# Sheet_1.net
KiCad netlist of a schematic drawn in EasyEDA
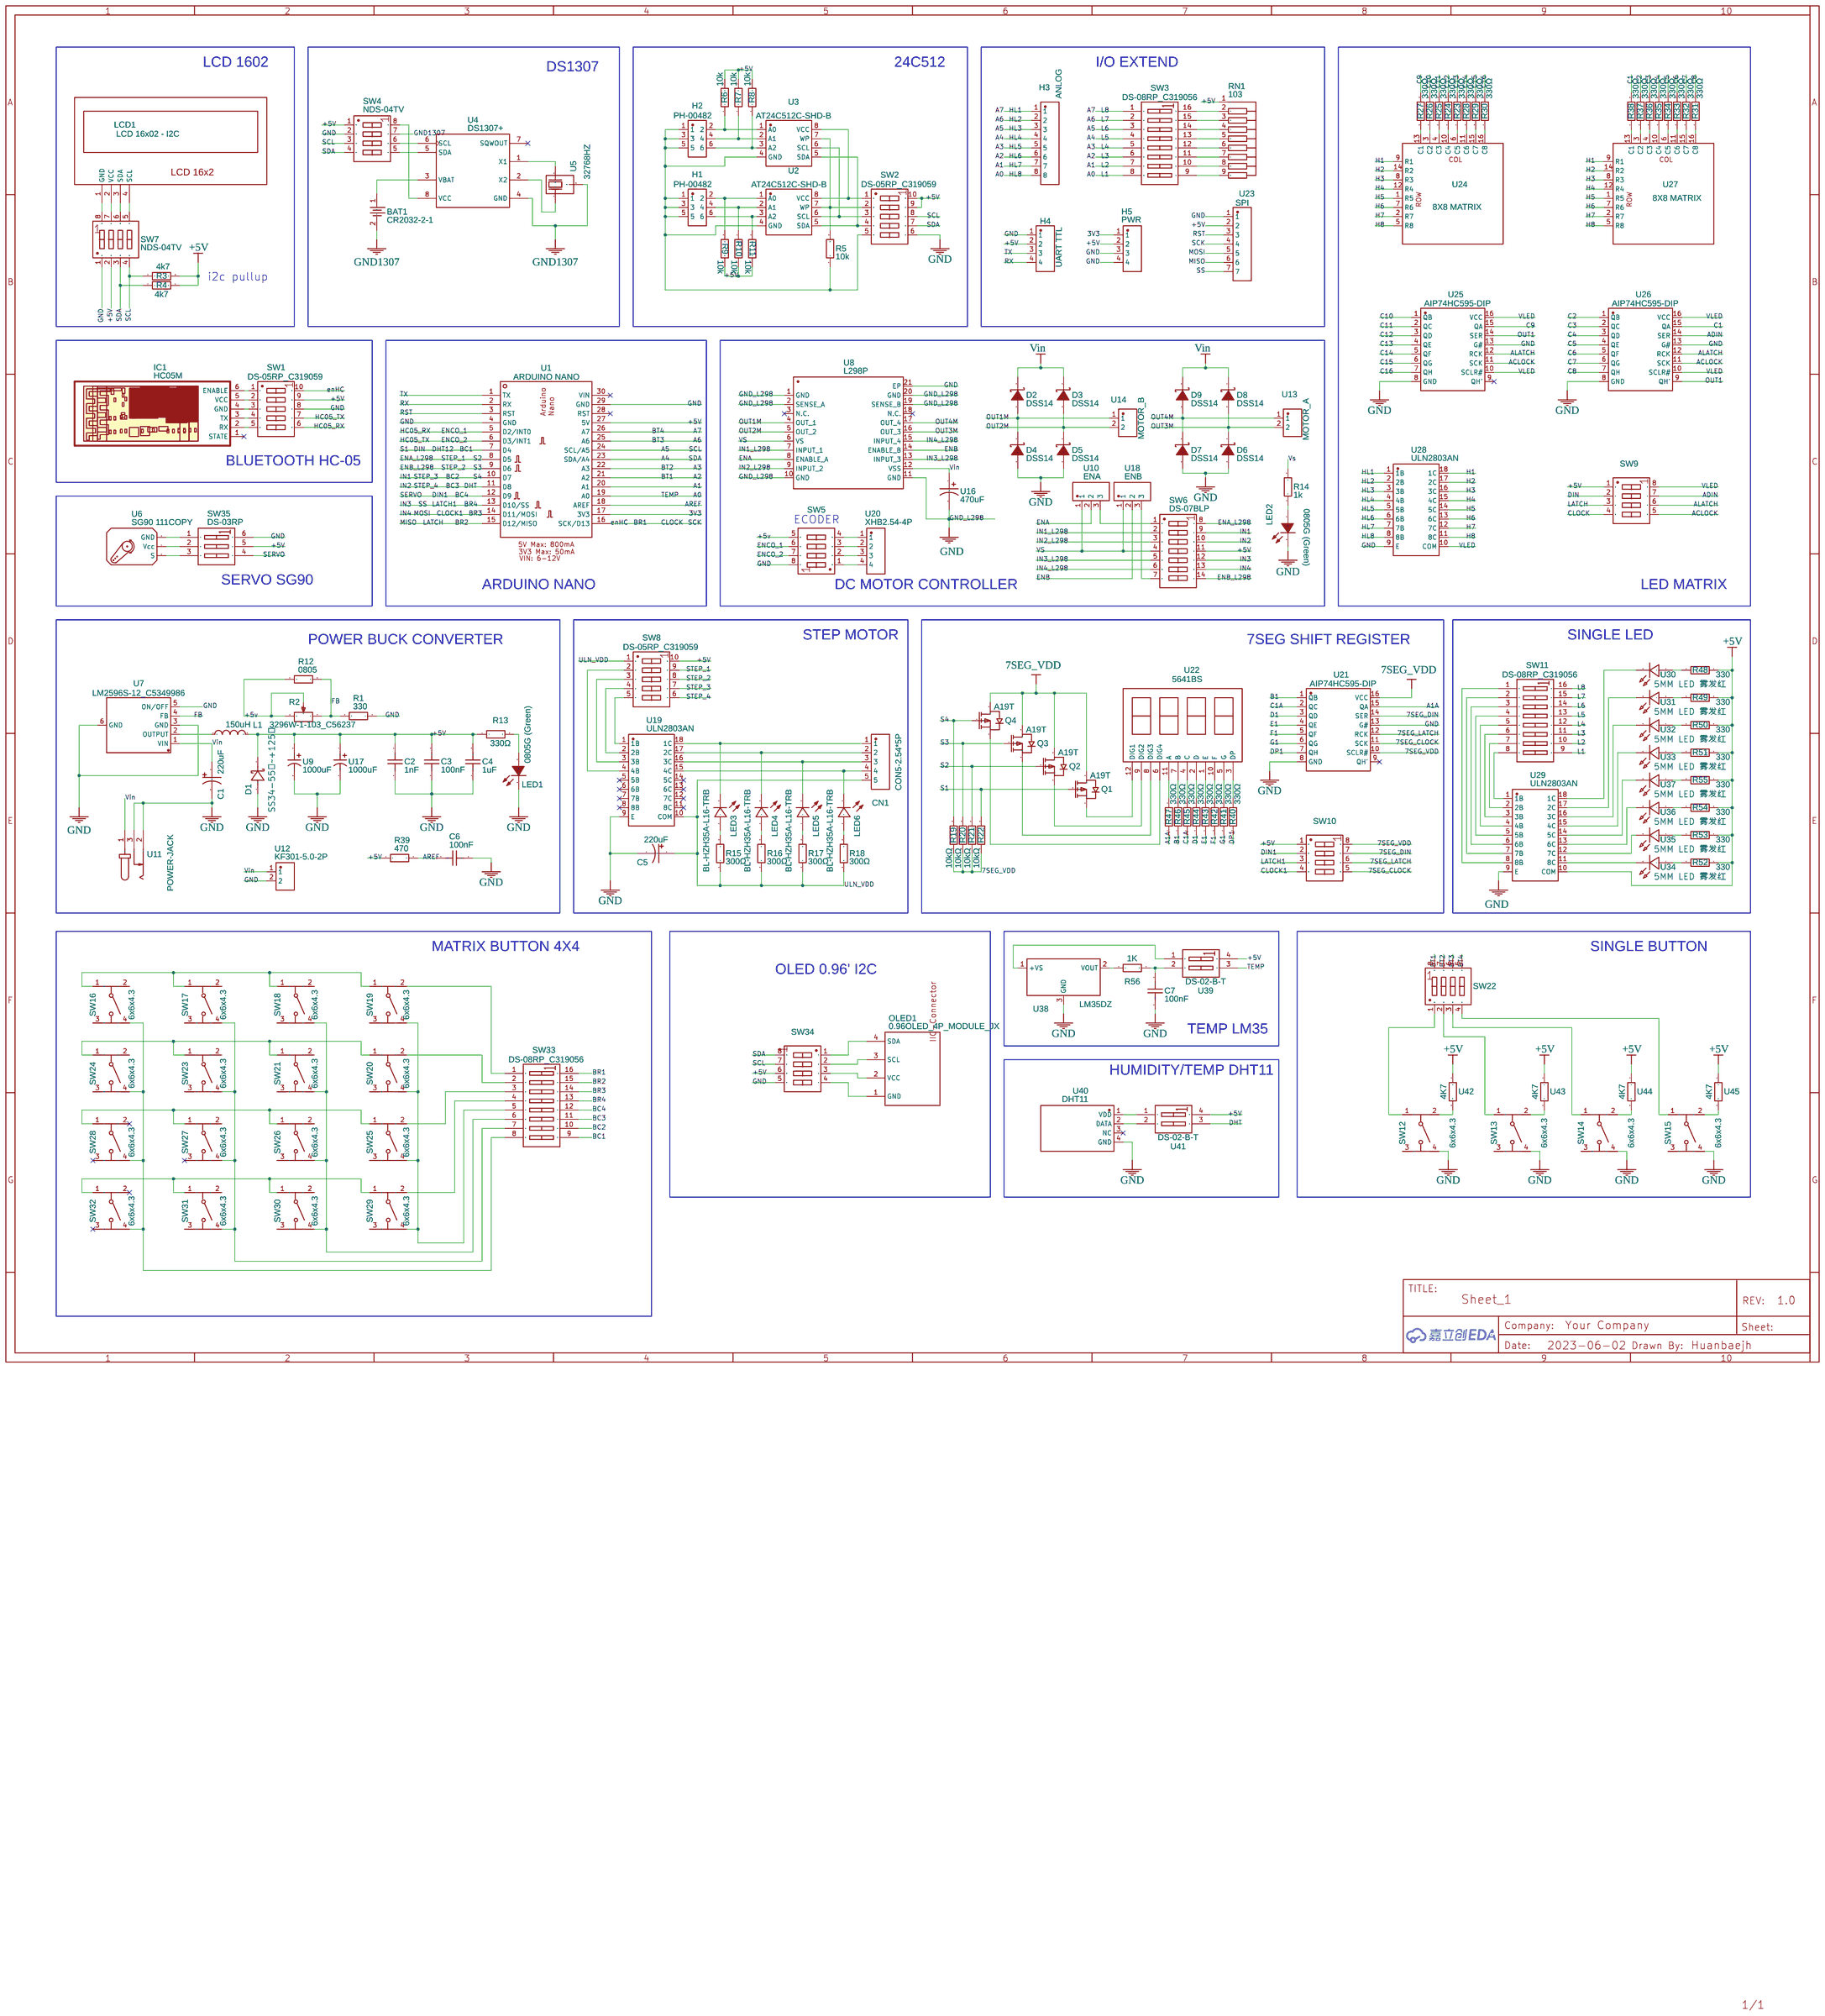
[diagram p0: schematic sheet]

(export (version "E")
  (design (tool "Eeschema 10.0.6"))
  (components
    (comp (ref "BAT1")
      (value "CR2032-2-1")
      (fields (field (name "BOM_Supplier Part") "C9900018737"))
      (libsource (lib "") (part "CR2032-2-1"))
    )
    (comp (ref "C1")
      (value "220uF")
      (fields
        (field (name "BOM_Manufacturer Part") "VUK221M1HTR-1316")
        (field (name "BOM_Supplier Part") "C335057")
      )
      (libsource (lib "") (part "VUK221M1HTR-1316"))
    )
    (comp (ref "C2")
      (value "1nF")
      (fields
        (field (name "BOM_Manufacturer Part") "C0805X102K101T")
        (field (name "BOM_Supplier Part") "C559288")
      )
      (libsource (lib "") (part "C0805X102K101T"))
    )
    (comp (ref "C3")
      (value "100nF")
      (fields
        (field (name "BOM_Manufacturer Part") "0805B104K101AT")
        (field (name "BOM_Supplier Part") "C3037660")
      )
      (libsource (lib "") (part "0805B104K101AT_2"))
    )
    (comp (ref "C4")
      (value "1uF")
      (fields
        (field (name "BOM_Manufacturer Part") "GRM219R71E105KA88D")
        (field (name "BOM_Supplier Part") "C86035")
      )
      (libsource (lib "") (part "GRM219R71E105KA88D"))
    )
    (comp (ref "C5")
      (value "220uF")
      (fields
        (field (name "BOM_Manufacturer Part") "EEEFC1C221AP")
        (field (name "BOM_Supplier Part") "C401620")
      )
      (libsource (lib "") (part "EEEFC1C221AP"))
    )
    (comp (ref "C6")
      (value "100nF")
      (fields
        (field (name "BOM_Manufacturer Part") "0805B104K101AT")
        (field (name "BOM_Supplier Part") "C3037660")
      )
      (libsource (lib "") (part "0805B104K101AT"))
    )
    (comp (ref "C7")
      (value "100nF")
      (fields
        (field (name "BOM_Manufacturer Part") "0805B104K101AT")
        (field (name "BOM_Supplier Part") "C3037660")
      )
      (libsource (lib "") (part "0805B104K101AT_1"))
    )
    (comp (ref "CN1")
      (value "CON5-2.54*5P")
      (fields (field (name "BOM_Supplier Part") "C9900003233"))
      (libsource (lib "") (part "CON5-2.54*5P"))
    )
    (comp (ref "D1")
      (value "SS34-55℃~+125℃")
      (fields
        (field (name "BOM_Manufacturer Part") "SS34-55℃&#126;+125℃")
        (field (name "BOM_Supplier Part") "C9900022445")
      )
      (libsource (lib "") (part "SS34-55℃&#126;+125℃"))
    )
    (comp (ref "D2")
      (value "DSS14")
      (fields (field (name "BOM_Supplier Part") "C59293"))
      (libsource (lib "") (part "DSS14"))
    )
    (comp (ref "D3")
      (value "DSS14")
      (fields (field (name "BOM_Supplier Part") "C59293"))
      (libsource (lib "") (part "DSS14"))
    )
    (comp (ref "D4")
      (value "DSS14")
      (fields (field (name "BOM_Supplier Part") "C59293"))
      (libsource (lib "") (part "DSS14"))
    )
    (comp (ref "D5")
      (value "DSS14")
      (fields (field (name "BOM_Supplier Part") "C59293"))
      (libsource (lib "") (part "DSS14"))
    )
    (comp (ref "D6")
      (value "DSS14")
      (fields (field (name "BOM_Supplier Part") "C59293"))
      (libsource (lib "") (part "DSS14"))
    )
    (comp (ref "D7")
      (value "DSS14")
      (fields (field (name "BOM_Supplier Part") "C59293"))
      (libsource (lib "") (part "DSS14"))
    )
    (comp (ref "D8")
      (value "DSS14")
      (fields (field (name "BOM_Supplier Part") "C59293"))
      (libsource (lib "") (part "DSS14"))
    )
    (comp (ref "D9")
      (value "DSS14")
      (fields (field (name "BOM_Supplier Part") "C59293"))
      (libsource (lib "") (part "DSS14"))
    )
    (comp (ref "H1")
      (value "PH-00482")
      (fields (field (name "BOM_Supplier Part") "C2685163"))
      (libsource (lib "") (part "PH-00482"))
    )
    (comp (ref "H2")
      (value "PH-00482")
      (fields (field (name "BOM_Supplier Part") "C2685163"))
      (libsource (lib "") (part "PH-00482"))
    )
    (comp (ref "H3")
      (value "ANLOG")
      (fields
        (field (name "BOM_Manufacturer Part") "X5511WV-08-C396D43-1220")
        (field (name "BOM_Supplier Part") "C2883395")
      )
      (libsource (lib "") (part "X5511WV-08-C396D43-1220"))
    )
    (comp (ref "H4")
      (value "UART TTL")
      (fields
        (field (name "BOM_Manufacturer Part") "A2541HWV-4P")
        (field (name "BOM_Supplier Part") "C5144876")
      )
      (libsource (lib "") (part "A2541HWV-4P_C5144876"))
    )
    (comp (ref "H5")
      (value "PWR")
      (fields
        (field (name "BOM_Manufacturer Part") "DZ254R-11-04-63")
        (field (name "BOM_Supplier Part") "C2935910")
      )
      (libsource (lib "") (part "DZ254R-11-04-63"))
    )
    (comp (ref "IC1") (value "HC05M") (libsource (lib "") (part "HC05M")))
    (comp (ref "L1")
      (value "150uH")
      (fields
        (field (name "BOM_Manufacturer Part") "SWRH1205B-151MT")
        (field (name "BOM_Supplier Part") "C127794")
      )
      (libsource (lib "") (part "SWRH1205B-151MT"))
    )
    (comp (ref "LCD1")
      (value "LCD 16x02 - I2C")
      (fields
        (field (name "BOM_Manufacturer Part") "LCM1602K-NSW-BBW-33V33")
        (field (name "BOM_Supplier Part") "C83272")
      )
      (libsource (lib "") (part "LCD 16x02 - I2C"))
    )
    (comp (ref "LED1")
      (value "0805G (Green)")
      (fields (field (name "BOM_Manufacturer Part") "KT-0805翠绿") (field (name "BOM_Supplier Part") "C2297"))
      (libsource (lib "") (part "0805G (Green)"))
    )
    (comp (ref "LED2")
      (value "0805G (Green)")
      (fields (field (name "BOM_Manufacturer Part") "KT-0805翠绿") (field (name "BOM_Supplier Part") "C2297"))
      (libsource (lib "") (part "0805G (Green)"))
    )
    (comp (ref "LED3")
      (value "BL-HZH35A-L16-TRB")
      (fields (field (name "BOM_Supplier Part") "C138554"))
      (libsource (lib "") (part "BL-HZH35A-L16-TRB"))
    )
    (comp (ref "LED4")
      (value "BL-HZH35A-L16-TRB")
      (fields (field (name "BOM_Supplier Part") "C138554"))
      (libsource (lib "") (part "BL-HZH35A-L16-TRB"))
    )
    (comp (ref "LED5")
      (value "BL-HZH35A-L16-TRB")
      (fields (field (name "BOM_Supplier Part") "C138554"))
      (libsource (lib "") (part "BL-HZH35A-L16-TRB"))
    )
    (comp (ref "LED6")
      (value "BL-HZH35A-L16-TRB")
      (fields (field (name "BOM_Supplier Part") "C138554"))
      (libsource (lib "") (part "BL-HZH35A-L16-TRB"))
    )
    (comp (ref "OLED1")
      (value "0.96OLED_4P_MODULE_JX")
      (fields (field (name "BOM_Supplier Part") "C9900004566"))
      (libsource (lib "") (part "0.96OLED_4P_MODULE_JX"))
    )
    (comp (ref "Q1")
      (value "A19T")
      (fields (field (name "BOM_Manufacturer Part") "FS3401M") (field (name "BOM_Supplier Part") "C2936839"))
      (libsource (lib "") (part "FS3401MLT1 A19T"))
    )
    (comp (ref "Q2")
      (value "A19T")
      (fields (field (name "BOM_Manufacturer Part") "FS3401M") (field (name "BOM_Supplier Part") "C2936839"))
      (libsource (lib "") (part "FS3401MLT1 A19T"))
    )
    (comp (ref "Q3")
      (value "A19T")
      (fields (field (name "BOM_Manufacturer Part") "FS3401M") (field (name "BOM_Supplier Part") "C2936839"))
      (libsource (lib "") (part "FS3401MLT1 A19T"))
    )
    (comp (ref "Q4")
      (value "A19T")
      (fields (field (name "BOM_Manufacturer Part") "FS3401M") (field (name "BOM_Supplier Part") "C2936839"))
      (libsource (lib "") (part "FS3401MLT1 A19T"))
    )
    (comp (ref "R1")
      (value "330")
      (fields
        (field (name "BOM_Manufacturer Part") "CR0805F833R2G")
        (field (name "BOM_Supplier Part") "C101670")
      )
      (libsource (lib "") (part "CR0805F833R2G"))
    )
    (comp (ref "R2")
      (value "3296W-1-103_C56237")
      (fields
        (field (name "BOM_Manufacturer Part") "3296W-1-103")
        (field (name "BOM_Supplier Part") "C56237")
      )
      (libsource (lib "") (part "3296W-1-103_C56237"))
    )
    (comp (ref "R3")
      (value "4k7")
      (fields
        (field (name "BOM_Manufacturer Part") "AECR0805F24K0K9")
        (field (name "BOM_Supplier Part") "C352238")
      )
      (libsource (lib "") (part "AECR0805F24K0K9"))
    )
    (comp (ref "R4")
      (value "4k7")
      (fields
        (field (name "BOM_Manufacturer Part") "AECR0805F24K0K9")
        (field (name "BOM_Supplier Part") "C352238")
      )
      (libsource (lib "") (part "AECR0805F24K0K9"))
    )
    (comp (ref "R5")
      (value "10k")
      (fields
        (field (name "BOM_Manufacturer Part") "CR0805F12K7P05Z")
        (field (name "BOM_Supplier Part") "C245233")
      )
      (libsource (lib "") (part "CR0805F12K7P05"))
    )
    (comp (ref "R6")
      (value "10k")
      (fields
        (field (name "BOM_Manufacturer Part") "CR0805F12K7P05Z")
        (field (name "BOM_Supplier Part") "C245233")
      )
      (libsource (lib "") (part "CR0805F12K7P05"))
    )
    (comp (ref "R7")
      (value "10k")
      (fields
        (field (name "BOM_Manufacturer Part") "CR0805F12K7P05Z")
        (field (name "BOM_Supplier Part") "C245233")
      )
      (libsource (lib "") (part "CR0805F12K7P05"))
    )
    (comp (ref "R8")
      (value "10k")
      (fields
        (field (name "BOM_Manufacturer Part") "CR0805F12K7P05Z")
        (field (name "BOM_Supplier Part") "C245233")
      )
      (libsource (lib "") (part "CR0805F12K7P05"))
    )
    (comp (ref "R9")
      (value "10k")
      (fields
        (field (name "BOM_Manufacturer Part") "CR0805F12K7P05Z")
        (field (name "BOM_Supplier Part") "C245233")
      )
      (libsource (lib "") (part "CR0805F12K7P05_1"))
    )
    (comp (ref "R10")
      (value "10k")
      (fields
        (field (name "BOM_Manufacturer Part") "CR0805F12K7P05Z")
        (field (name "BOM_Supplier Part") "C245233")
      )
      (libsource (lib "") (part "CR0805F12K7P05_1"))
    )
    (comp (ref "R11")
      (value "10k")
      (fields
        (field (name "BOM_Manufacturer Part") "CR0805F12K7P05Z")
        (field (name "BOM_Supplier Part") "C245233")
      )
      (libsource (lib "") (part "CR0805F12K7P05_1"))
    )
    (comp (ref "R12")
      (value "0805")
      (fields (field (name "BOM_Supplier Part") "C9900012715"))
      (libsource (lib "") (part "0805"))
    )
    (comp (ref "R13")
      (value "330Ω")
      (fields
        (field (name "BOM_Manufacturer Part") "AECR0805F130RK9")
        (field (name "BOM_Supplier Part") "C352269")
      )
      (libsource (lib "") (part "AECR0805F130RK9"))
    )
    (comp (ref "R14")
      (value "1k")
      (fields
        (field (name "BOM_Manufacturer Part") "AECR0805F130RK9")
        (field (name "BOM_Supplier Part") "C352269")
      )
      (libsource (lib "") (part "AECR0805F130RK9_1"))
    )
    (comp (ref "R15")
      (value "300Ω")
      (fields
        (field (name "BOM_Manufacturer Part") "AECR0805F300RK9")
        (field (name "BOM_Supplier Part") "C352224")
      )
      (libsource (lib "") (part "AECR0805F300RK9"))
    )
    (comp (ref "R16")
      (value "300Ω")
      (fields
        (field (name "BOM_Manufacturer Part") "AECR0805F300RK9")
        (field (name "BOM_Supplier Part") "C352224")
      )
      (libsource (lib "") (part "AECR0805F300RK9"))
    )
    (comp (ref "R17")
      (value "300Ω")
      (fields
        (field (name "BOM_Manufacturer Part") "AECR0805F300RK9")
        (field (name "BOM_Supplier Part") "C352224")
      )
      (libsource (lib "") (part "AECR0805F300RK9"))
    )
    (comp (ref "R18")
      (value "300Ω")
      (fields
        (field (name "BOM_Manufacturer Part") "AECR0805F300RK9")
        (field (name "BOM_Supplier Part") "C352224")
      )
      (libsource (lib "") (part "AECR0805F300RK9"))
    )
    (comp (ref "R19")
      (value "10kΩ")
      (fields
        (field (name "BOM_Manufacturer Part") "0805WAD1002T5E")
        (field (name "BOM_Supplier Part") "C169071")
      )
      (libsource (lib "") (part "0805WAD1002T5E"))
    )
    (comp (ref "R20")
      (value "10kΩ")
      (fields
        (field (name "BOM_Manufacturer Part") "0805WAD1002T5E")
        (field (name "BOM_Supplier Part") "C169071")
      )
      (libsource (lib "") (part "0805WAD1002T5E"))
    )
    (comp (ref "R21")
      (value "10kΩ")
      (fields
        (field (name "BOM_Manufacturer Part") "0805WAD1002T5E")
        (field (name "BOM_Supplier Part") "C169071")
      )
      (libsource (lib "") (part "0805WAD1002T5E"))
    )
    (comp (ref "R22")
      (value "10kΩ")
      (fields
        (field (name "BOM_Manufacturer Part") "0805WAD1002T5E")
        (field (name "BOM_Supplier Part") "C169071")
      )
      (libsource (lib "") (part "0805WAD1002T5E"))
    )
    (comp (ref "R23")
      (value "330Ω")
      (fields
        (field (name "BOM_Manufacturer Part") "CR0805J80331G")
        (field (name "BOM_Supplier Part") "C101994")
      )
      (libsource (lib "") (part "CR0805J80331G"))
    )
    (comp (ref "R24")
      (value "330Ω")
      (fields
        (field (name "BOM_Manufacturer Part") "CR0805J80331G")
        (field (name "BOM_Supplier Part") "C101994")
      )
      (libsource (lib "") (part "CR0805J80331G"))
    )
    (comp (ref "R25")
      (value "330Ω")
      (fields
        (field (name "BOM_Manufacturer Part") "CR0805J80331G")
        (field (name "BOM_Supplier Part") "C101994")
      )
      (libsource (lib "") (part "CR0805J80331G"))
    )
    (comp (ref "R26")
      (value "330Ω")
      (fields
        (field (name "BOM_Manufacturer Part") "CR0805J80331G")
        (field (name "BOM_Supplier Part") "C101994")
      )
      (libsource (lib "") (part "CR0805J80331G"))
    )
    (comp (ref "R27")
      (value "330Ω")
      (fields
        (field (name "BOM_Manufacturer Part") "CR0805J80331G")
        (field (name "BOM_Supplier Part") "C101994")
      )
      (libsource (lib "") (part "CR0805J80331G"))
    )
    (comp (ref "R28")
      (value "330Ω")
      (fields
        (field (name "BOM_Manufacturer Part") "CR0805J80331G")
        (field (name "BOM_Supplier Part") "C101994")
      )
      (libsource (lib "") (part "CR0805J80331G"))
    )
    (comp (ref "R29")
      (value "330Ω")
      (fields
        (field (name "BOM_Manufacturer Part") "CR0805J80331G")
        (field (name "BOM_Supplier Part") "C101994")
      )
      (libsource (lib "") (part "CR0805J80331G"))
    )
    (comp (ref "R30")
      (value "330Ω")
      (fields
        (field (name "BOM_Manufacturer Part") "CR0805J80331G")
        (field (name "BOM_Supplier Part") "C101994")
      )
      (libsource (lib "") (part "CR0805J80331G"))
    )
    (comp (ref "R31")
      (value "330Ω")
      (fields
        (field (name "BOM_Manufacturer Part") "CR0805J80331G")
        (field (name "BOM_Supplier Part") "C101994")
      )
      (libsource (lib "") (part "CR0805J80331G"))
    )
    (comp (ref "R32")
      (value "330Ω")
      (fields
        (field (name "BOM_Manufacturer Part") "CR0805J80331G")
        (field (name "BOM_Supplier Part") "C101994")
      )
      (libsource (lib "") (part "CR0805J80331G"))
    )
    (comp (ref "R33")
      (value "330Ω")
      (fields
        (field (name "BOM_Manufacturer Part") "CR0805J80331G")
        (field (name "BOM_Supplier Part") "C101994")
      )
      (libsource (lib "") (part "CR0805J80331G"))
    )
    (comp (ref "R34")
      (value "330Ω")
      (fields
        (field (name "BOM_Manufacturer Part") "CR0805J80331G")
        (field (name "BOM_Supplier Part") "C101994")
      )
      (libsource (lib "") (part "CR0805J80331G"))
    )
    (comp (ref "R35")
      (value "330Ω")
      (fields
        (field (name "BOM_Manufacturer Part") "CR0805J80331G")
        (field (name "BOM_Supplier Part") "C101994")
      )
      (libsource (lib "") (part "CR0805J80331G"))
    )
    (comp (ref "R36")
      (value "330Ω")
      (fields
        (field (name "BOM_Manufacturer Part") "CR0805J80331G")
        (field (name "BOM_Supplier Part") "C101994")
      )
      (libsource (lib "") (part "CR0805J80331G"))
    )
    (comp (ref "R37")
      (value "330Ω")
      (fields
        (field (name "BOM_Manufacturer Part") "CR0805J80331G")
        (field (name "BOM_Supplier Part") "C101994")
      )
      (libsource (lib "") (part "CR0805J80331G"))
    )
    (comp (ref "R38")
      (value "330Ω")
      (fields
        (field (name "BOM_Manufacturer Part") "CR0805J80331G")
        (field (name "BOM_Supplier Part") "C101994")
      )
      (libsource (lib "") (part "CR0805J80331G"))
    )
    (comp (ref "R39")
      (value "470")
      (fields
        (field (name "BOM_Manufacturer Part") "CR0805-FX-47R0ELF")
        (field (name "BOM_Supplier Part") "C204532")
      )
      (libsource (lib "") (part "CR0805-FX-47R0ELF"))
    )
    (comp (ref "R40")
      (value "330Ω")
      (fields
        (field (name "BOM_Manufacturer Part") "CR0805J80331G")
        (field (name "BOM_Supplier Part") "C101994")
      )
      (libsource (lib "") (part "CR0805J80331G"))
    )
    (comp (ref "R41")
      (value "330Ω")
      (fields
        (field (name "BOM_Manufacturer Part") "CR0805J80331G")
        (field (name "BOM_Supplier Part") "C101994")
      )
      (libsource (lib "") (part "CR0805J80331G"))
    )
    (comp (ref "R42")
      (value "330Ω")
      (fields
        (field (name "BOM_Manufacturer Part") "CR0805J80331G")
        (field (name "BOM_Supplier Part") "C101994")
      )
      (libsource (lib "") (part "CR0805J80331G"))
    )
    (comp (ref "R43")
      (value "330Ω")
      (fields
        (field (name "BOM_Manufacturer Part") "CR0805J80331G")
        (field (name "BOM_Supplier Part") "C101994")
      )
      (libsource (lib "") (part "CR0805J80331G"))
    )
    (comp (ref "R44")
      (value "330Ω")
      (fields
        (field (name "BOM_Manufacturer Part") "CR0805J80331G")
        (field (name "BOM_Supplier Part") "C101994")
      )
      (libsource (lib "") (part "CR0805J80331G"))
    )
    (comp (ref "R45")
      (value "330Ω")
      (fields
        (field (name "BOM_Manufacturer Part") "CR0805J80331G")
        (field (name "BOM_Supplier Part") "C101994")
      )
      (libsource (lib "") (part "CR0805J80331G"))
    )
    (comp (ref "R46")
      (value "330Ω")
      (fields
        (field (name "BOM_Manufacturer Part") "CR0805J80331G")
        (field (name "BOM_Supplier Part") "C101994")
      )
      (libsource (lib "") (part "CR0805J80331G"))
    )
    (comp (ref "R47")
      (value "330Ω")
      (fields
        (field (name "BOM_Manufacturer Part") "CR0805J80331G")
        (field (name "BOM_Supplier Part") "C101994")
      )
      (libsource (lib "") (part "CR0805J80331G"))
    )
    (comp (ref "R48")
      (value "330")
      (fields
        (field (name "BOM_Manufacturer Part") "AECR0805F160RK9")
        (field (name "BOM_Supplier Part") "C352264")
      )
      (libsource (lib "") (part "AECR0805F160RK9"))
    )
    (comp (ref "R49")
      (value "330")
      (fields
        (field (name "BOM_Manufacturer Part") "AECR0805F160RK9")
        (field (name "BOM_Supplier Part") "C352264")
      )
      (libsource (lib "") (part "AECR0805F160RK9"))
    )
    (comp (ref "R50")
      (value "330")
      (fields
        (field (name "BOM_Manufacturer Part") "AECR0805F160RK9")
        (field (name "BOM_Supplier Part") "C352264")
      )
      (libsource (lib "") (part "AECR0805F160RK9"))
    )
    (comp (ref "R51")
      (value "330")
      (fields
        (field (name "BOM_Manufacturer Part") "AECR0805F160RK9")
        (field (name "BOM_Supplier Part") "C352264")
      )
      (libsource (lib "") (part "AECR0805F160RK9"))
    )
    (comp (ref "R52")
      (value "330")
      (fields
        (field (name "BOM_Manufacturer Part") "AECR0805F160RK9")
        (field (name "BOM_Supplier Part") "C352264")
      )
      (libsource (lib "") (part "AECR0805F160RK9"))
    )
    (comp (ref "R53")
      (value "330")
      (fields
        (field (name "BOM_Manufacturer Part") "AECR0805F160RK9")
        (field (name "BOM_Supplier Part") "C352264")
      )
      (libsource (lib "") (part "AECR0805F160RK9"))
    )
    (comp (ref "R54")
      (value "330")
      (fields
        (field (name "BOM_Manufacturer Part") "AECR0805F160RK9")
        (field (name "BOM_Supplier Part") "C352264")
      )
      (libsource (lib "") (part "AECR0805F160RK9"))
    )
    (comp (ref "R55")
      (value "330")
      (fields
        (field (name "BOM_Manufacturer Part") "AECR0805F160RK9")
        (field (name "BOM_Supplier Part") "C352264")
      )
      (libsource (lib "") (part "AECR0805F160RK9"))
    )
    (comp (ref "R56")
      (value "1K")
      (fields
        (field (name "BOM_Manufacturer Part") "CR0805-FX-47R0ELF")
        (field (name "BOM_Supplier Part") "C204532")
      )
      (libsource (lib "") (part "CR0805-FX-47R0ELF"))
    )
    (comp (ref "RN1")
      (value "103")
      (fields (field (name "BOM_Manufacturer Part") "RAA09331G") (field (name "BOM_Supplier Part") "C353617"))
      (libsource (lib "") (part "RAA09331G"))
    )
    (comp (ref "SW1")
      (value "DS-05RP_C319059")
      (fields (field (name "BOM_Manufacturer Part") "DS-05RP") (field (name "BOM_Supplier Part") "C319059"))
      (libsource (lib "") (part "DS-05RP_C319059"))
    )
    (comp (ref "SW2")
      (value "DS-05RP_C319059")
      (fields (field (name "BOM_Manufacturer Part") "DS-05RP") (field (name "BOM_Supplier Part") "C319059"))
      (libsource (lib "") (part "DS-05RP_C319059"))
    )
    (comp (ref "SW3")
      (value "DS-08RP_C319056")
      (fields (field (name "BOM_Manufacturer Part") "DS-08RP") (field (name "BOM_Supplier Part") "C319056"))
      (libsource (lib "") (part "DS-08RP_C319056"))
    )
    (comp (ref "SW4")
      (value "NDS-04TV")
      (fields (field (name "BOM_Supplier Part") "C699468"))
      (libsource (lib "") (part "NDS-04TV"))
    )
    (comp (ref "SW5")
      (value "NDS-04TV")
      (fields (field (name "BOM_Supplier Part") "C699468"))
      (libsource (lib "") (part "NDS-04TV_4"))
    )
    (comp (ref "SW6")
      (value "DS-07BLP")
      (fields (field (name "BOM_Supplier Part") "C692505"))
      (libsource (lib "") (part "DS-07BLP"))
    )
    (comp (ref "SW7")
      (value "NDS-04TV")
      (fields (field (name "BOM_Supplier Part") "C699468"))
      (libsource (lib "") (part "NDS-04TV_2"))
    )
    (comp (ref "SW8")
      (value "DS-05RP_C319059")
      (fields (field (name "BOM_Manufacturer Part") "DS-05RP") (field (name "BOM_Supplier Part") "C319059"))
      (libsource (lib "") (part "DS-05RP_C319059"))
    )
    (comp (ref "SW9")
      (value "NDS-04TV")
      (fields (field (name "BOM_Supplier Part") "C699468"))
      (libsource (lib "") (part "NDS-04TV"))
    )
    (comp (ref "SW10")
      (value "NDS-04TV")
      (fields (field (name "BOM_Supplier Part") "C699468"))
      (libsource (lib "") (part "NDS-04TV"))
    )
    (comp (ref "SW11")
      (value "DS-08RP_C319056")
      (fields (field (name "BOM_Manufacturer Part") "DS-08RP") (field (name "BOM_Supplier Part") "C319056"))
      (libsource (lib "") (part "DS-08RP_C319056"))
    )
    (comp (ref "SW12")
      (value "6x6x4.3")
      (fields (field (name "BOM_Supplier Part") "C10913"))
      (libsource (lib "") (part "6x6x4.3_2"))
    )
    (comp (ref "SW13")
      (value "6x6x4.3")
      (fields (field (name "BOM_Supplier Part") "C10913"))
      (libsource (lib "") (part "6x6x4.3_2"))
    )
    (comp (ref "SW14")
      (value "6x6x4.3")
      (fields (field (name "BOM_Supplier Part") "C10913"))
      (libsource (lib "") (part "6x6x4.3_2"))
    )
    (comp (ref "SW15")
      (value "6x6x4.3")
      (fields (field (name "BOM_Supplier Part") "C10913"))
      (libsource (lib "") (part "6x6x4.3_2"))
    )
    (comp (ref "SW16")
      (value "6x6x4.3")
      (fields (field (name "BOM_Supplier Part") "C10913"))
      (libsource (lib "") (part "6x6x4.3_2"))
    )
    (comp (ref "SW17")
      (value "6x6x4.3")
      (fields (field (name "BOM_Supplier Part") "C10913"))
      (libsource (lib "") (part "6x6x4.3"))
    )
    (comp (ref "SW18")
      (value "6x6x4.3")
      (fields (field (name "BOM_Supplier Part") "C10913"))
      (libsource (lib "") (part "6x6x4.3_1"))
    )
    (comp (ref "SW19")
      (value "6x6x4.3")
      (fields (field (name "BOM_Supplier Part") "C10913"))
      (libsource (lib "") (part "6x6x4.3_3"))
    )
    (comp (ref "SW20")
      (value "6x6x4.3")
      (fields (field (name "BOM_Supplier Part") "C10913"))
      (libsource (lib "") (part "6x6x4.3_3"))
    )
    (comp (ref "SW21")
      (value "6x6x4.3")
      (fields (field (name "BOM_Supplier Part") "C10913"))
      (libsource (lib "") (part "6x6x4.3_1"))
    )
    (comp (ref "SW22")
      (value "NDS-04TV")
      (fields (field (name "BOM_Supplier Part") "C699468"))
      (libsource (lib "") (part "NDS-04TV_1"))
    )
    (comp (ref "SW23")
      (value "6x6x4.3")
      (fields (field (name "BOM_Supplier Part") "C10913"))
      (libsource (lib "") (part "6x6x4.3"))
    )
    (comp (ref "SW24")
      (value "6x6x4.3")
      (fields (field (name "BOM_Supplier Part") "C10913"))
      (libsource (lib "") (part "6x6x4.3_2"))
    )
    (comp (ref "SW25")
      (value "6x6x4.3")
      (fields (field (name "BOM_Supplier Part") "C10913"))
      (libsource (lib "") (part "6x6x4.3_3"))
    )
    (comp (ref "SW26")
      (value "6x6x4.3")
      (fields (field (name "BOM_Supplier Part") "C10913"))
      (libsource (lib "") (part "6x6x4.3_1"))
    )
    (comp (ref "SW27")
      (value "6x6x4.3")
      (fields (field (name "BOM_Supplier Part") "C10913"))
      (libsource (lib "") (part "6x6x4.3"))
    )
    (comp (ref "SW28")
      (value "6x6x4.3")
      (fields (field (name "BOM_Supplier Part") "C10913"))
      (libsource (lib "") (part "6x6x4.3_2"))
    )
    (comp (ref "SW29")
      (value "6x6x4.3")
      (fields (field (name "BOM_Supplier Part") "C10913"))
      (libsource (lib "") (part "6x6x4.3_3"))
    )
    (comp (ref "SW30")
      (value "6x6x4.3")
      (fields (field (name "BOM_Supplier Part") "C10913"))
      (libsource (lib "") (part "6x6x4.3_1"))
    )
    (comp (ref "SW31")
      (value "6x6x4.3")
      (fields (field (name "BOM_Supplier Part") "C10913"))
      (libsource (lib "") (part "6x6x4.3"))
    )
    (comp (ref "SW32")
      (value "6x6x4.3")
      (fields (field (name "BOM_Supplier Part") "C10913"))
      (libsource (lib "") (part "6x6x4.3_2"))
    )
    (comp (ref "SW33")
      (value "DS-08RP_C319056")
      (fields (field (name "BOM_Manufacturer Part") "DS-08RP") (field (name "BOM_Supplier Part") "C319056"))
      (libsource (lib "") (part "DS-08RP_C319056"))
    )
    (comp (ref "SW34")
      (value "NDS-04TV")
      (fields (field (name "BOM_Supplier Part") "C699468"))
      (libsource (lib "") (part "NDS-04TV_3"))
    )
    (comp (ref "SW35")
      (value "DS-03RP")
      (fields (field (name "BOM_Supplier Part") "C129060"))
      (libsource (lib "") (part "DS-03RP"))
    )
    (comp (ref "U1") (value "ARDUINO NANO") (libsource (lib "") (part "ARDUINO NANO")))
    (comp (ref "U2")
      (value "AT24C512C-SHD-B")
      (fields (field (name "BOM_Supplier Part") "C615464"))
      (libsource (lib "") (part "AT24C512C-SHD-B"))
    )
    (comp (ref "U3")
      (value "AT24C512C-SHD-B")
      (fields (field (name "BOM_Supplier Part") "C615464"))
      (libsource (lib "") (part "AT24C512C-SHD-B"))
    )
    (comp (ref "U4")
      (value "DS1307+")
      (fields (field (name "BOM_Supplier Part") "C59267"))
      (libsource (lib "") (part "DS1307+"))
    )
    (comp (ref "U5")
      (value "32768HZ")
      (fields
        (field (name "BOM_Manufacturer Part") "32768Hz-CRYSTAL_2x6SMD")
        (field (name "BOM_Supplier Part") "C9900008919")
      )
      (libsource (lib "") (part "32768HZ-CRYSTAL_2X6SMD"))
    )
    (comp (ref "U6") (value "SG90 111COPY") (libsource (lib "") (part "SG90 111COPY")))
    (comp (ref "U7")
      (value "LM2596S-12_C5349986")
      (fields
        (field (name "BOM_Manufacturer Part") "LM2596S-12")
        (field (name "BOM_Supplier Part") "C5349986")
      )
      (libsource (lib "") (part "LM2596S-12_C5349986"))
    )
    (comp (ref "U8")
      (value "L298P")
      (fields (field (name "BOM_Supplier Part") "C85595"))
      (libsource (lib "") (part "L298P"))
    )
    (comp (ref "U9")
      (value "1000uF")
      (fields
        (field (name "BOM_Manufacturer Part") "10TZV1000M10X10.5")
        (field (name "BOM_Supplier Part") "C2163745")
      )
      (libsource (lib "") (part "10TZV1000M10X10.5"))
    )
    (comp (ref "U10")
      (value "ENA")
      (fields
        (field (name "BOM_Manufacturer Part") "PEC03SAAN")
        (field (name "BOM_Supplier Part") "C9900020756")
      )
      (libsource (lib "") (part "PEC03SAAN"))
    )
    (comp (ref "U11")
      (value "POWER-JACK")
      (fields (field (name "BOM_Supplier Part") "C9900001795"))
      (libsource (lib "") (part "POWER-JACK"))
    )
    (comp (ref "U12")
      (value "KF301-5.0-2P")
      (fields (field (name "BOM_Supplier Part") "C474881"))
      (libsource (lib "") (part "KF301-5.0-2P"))
    )
    (comp (ref "U13")
      (value "MOTOR_A")
      (fields
        (field (name "BOM_Manufacturer Part") "KF301-5.0-2P")
        (field (name "BOM_Supplier Part") "C474881")
      )
      (libsource (lib "") (part "KF301-5.0-2P"))
    )
    (comp (ref "U14")
      (value "MOTOR_B")
      (fields
        (field (name "BOM_Manufacturer Part") "KF301-5.0-2P")
        (field (name "BOM_Supplier Part") "C474881")
      )
      (libsource (lib "") (part "KF301-5.0-2P"))
    )
    (comp (ref "U16")
      (value "470uF")
      (fields
        (field (name "BOM_Manufacturer Part") "10SGV470M10X10.5")
        (field (name "BOM_Supplier Part") "C1896542")
      )
      (libsource (lib "") (part "10SGV470M10X10.5"))
    )
    (comp (ref "U17")
      (value "1000uF")
      (fields
        (field (name "BOM_Manufacturer Part") "10TZV1000M10X10.5")
        (field (name "BOM_Supplier Part") "C2163745")
      )
      (libsource (lib "") (part "10TZV1000M10X10.5"))
    )
    (comp (ref "U18")
      (value "ENB")
      (fields
        (field (name "BOM_Manufacturer Part") "PEC03SAAN")
        (field (name "BOM_Supplier Part") "C9900020756")
      )
      (libsource (lib "") (part "PEC03SAAN"))
    )
    (comp (ref "U19")
      (value "ULN2803AN")
      (fields (field (name "BOM_Supplier Part") "C481685"))
      (libsource (lib "") (part "ULN2803AN"))
    )
    (comp (ref "U20")
      (value "XHB2.54-4P")
      (fields (field (name "BOM_Supplier Part") "C9900014704"))
      (libsource (lib "") (part "XHB2.54-4P"))
    )
    (comp (ref "U21")
      (value "AIP74HC595-DIP")
      (fields (field (name "BOM_Supplier Part") "C112387"))
      (libsource (lib "") (part "AIP74HC595-DIP"))
    )
    (comp (ref "U22")
      (value "5641BS")
      (fields (field (name "BOM_Manufacturer Part") "KEM-5641-BSR"))
      (libsource (lib "") (part "KEM-5641-BSR"))
    )
    (comp (ref "U23")
      (value "SPI")
      (fields
        (field (name "BOM_Manufacturer Part") "PZ254-1-07-Z-C")
        (field (name "BOM_Supplier Part") "C5156434")
      )
      (libsource (lib "") (part "PZ254-1-07-Z-C"))
    )
    (comp (ref "U24")
      (value "8X8 MATRIX")
      (fields (field (name "BOM_Manufacturer Part") "1088AS_dotmatrix"))
      (libsource (lib "") (part "8X8 MATRIX"))
    )
    (comp (ref "U25")
      (value "AIP74HC595-DIP")
      (fields (field (name "BOM_Supplier Part") "C112387"))
      (libsource (lib "") (part "AIP74HC595-DIP"))
    )
    (comp (ref "U26")
      (value "AIP74HC595-DIP")
      (fields (field (name "BOM_Supplier Part") "C112387"))
      (libsource (lib "") (part "AIP74HC595-DIP"))
    )
    (comp (ref "U27")
      (value "8X8 MATRIX")
      (fields (field (name "BOM_Manufacturer Part") "1088AS_dotmatrix"))
      (libsource (lib "") (part "8X8 MATRIX"))
    )
    (comp (ref "U28")
      (value "ULN2803AN")
      (fields (field (name "BOM_Supplier Part") "C481685"))
      (libsource (lib "") (part "ULN2803AN"))
    )
    (comp (ref "U29")
      (value "ULN2803AN")
      (fields (field (name "BOM_Supplier Part") "C481685"))
      (libsource (lib "") (part "ULN2803AN"))
    )
    (comp (ref "U30")
      (value "5MM LED 雾发红")
      (fields
        (field (name "BOM_Manufacturer Part") "5mm LED 雾发红")
        (field (name "BOM_Supplier Part") "C9900034380")
      )
      (libsource (lib "") (part "5MM LED 雾发红"))
    )
    (comp (ref "U31")
      (value "5MM LED 雾发红")
      (fields
        (field (name "BOM_Manufacturer Part") "5mm LED 雾发红")
        (field (name "BOM_Supplier Part") "C9900034380")
      )
      (libsource (lib "") (part "5MM LED 雾发红"))
    )
    (comp (ref "U32")
      (value "5MM LED 雾发红")
      (fields
        (field (name "BOM_Manufacturer Part") "5mm LED 雾发红")
        (field (name "BOM_Supplier Part") "C9900034380")
      )
      (libsource (lib "") (part "5MM LED 雾发红"))
    )
    (comp (ref "U33")
      (value "5MM LED 雾发红")
      (fields
        (field (name "BOM_Manufacturer Part") "5mm LED 雾发红")
        (field (name "BOM_Supplier Part") "C9900034380")
      )
      (libsource (lib "") (part "5MM LED 雾发红"))
    )
    (comp (ref "U34")
      (value "5MM LED 雾发红")
      (fields
        (field (name "BOM_Manufacturer Part") "5mm LED 雾发红")
        (field (name "BOM_Supplier Part") "C9900034380")
      )
      (libsource (lib "") (part "5MM LED 雾发红"))
    )
    (comp (ref "U35")
      (value "5MM LED 雾发红")
      (fields
        (field (name "BOM_Manufacturer Part") "5mm LED 雾发红")
        (field (name "BOM_Supplier Part") "C9900034380")
      )
      (libsource (lib "") (part "5MM LED 雾发红"))
    )
    (comp (ref "U36")
      (value "5MM LED 雾发红")
      (fields
        (field (name "BOM_Manufacturer Part") "5mm LED 雾发红")
        (field (name "BOM_Supplier Part") "C9900034380")
      )
      (libsource (lib "") (part "5MM LED 雾发红"))
    )
    (comp (ref "U37")
      (value "5MM LED 雾发红")
      (fields
        (field (name "BOM_Manufacturer Part") "5mm LED 雾发红")
        (field (name "BOM_Supplier Part") "C9900034380")
      )
      (libsource (lib "") (part "5MM LED 雾发红"))
    )
    (comp (ref "U38")
      (value "LM35DZ")
      (fields
        (field (name "BOM_Manufacturer Part") "LM35DZ/NOPB")
        (field (name "BOM_Supplier Part") "C12165")
      )
      (libsource (lib "") (part "LM35DZ"))
    )
    (comp (ref "U39")
      (value "DS-02-B-T")
      (fields (field (name "BOM_Supplier Part") "C5162136"))
      (libsource (lib "") (part "DS-02-B-T"))
    )
    (comp (ref "U40")
      (value "DHT11")
      (fields (field (name "BOM_Supplier Part") "C117051"))
      (libsource (lib "") (part "DHT11"))
    )
    (comp (ref "U41")
      (value "DS-02-B-T")
      (fields (field (name "BOM_Supplier Part") "C5162136"))
      (libsource (lib "") (part "DS-02-B-T"))
    )
    (comp (ref "U42")
      (value "4K7")
      (fields
        (field (name "BOM_Manufacturer Part") "CR0805-JW-104ELF")
        (field (name "BOM_Supplier Part") "C9900011175")
      )
      (libsource (lib "") (part "CR0805-JW-104ELF"))
    )
    (comp (ref "U43")
      (value "4K7")
      (fields
        (field (name "BOM_Manufacturer Part") "CR0805-JW-104ELF")
        (field (name "BOM_Supplier Part") "C9900011175")
      )
      (libsource (lib "") (part "CR0805-JW-104ELF"))
    )
    (comp (ref "U44")
      (value "4K7")
      (fields
        (field (name "BOM_Manufacturer Part") "CR0805-JW-104ELF")
        (field (name "BOM_Supplier Part") "C9900011175")
      )
      (libsource (lib "") (part "CR0805-JW-104ELF"))
    )
    (comp (ref "U45")
      (value "4K7")
      (fields
        (field (name "BOM_Manufacturer Part") "CR0805-JW-104ELF")
        (field (name "BOM_Supplier Part") "C9900011175")
      )
      (libsource (lib "") (part "CR0805-JW-104ELF"))
    )
  )
  (nets
    (net (code "1") (name "+5V") (class "Default")
      (node (ref "C2") (pin "2") (pinfunction "2_2") (pintype "unspecified"))
      (node (ref "C3") (pin "2") (pinfunction "2_2") (pintype "unspecified"))
      (node (ref "C4") (pin "2") (pinfunction "2_2") (pintype "unspecified"))
      (node (ref "D1") (pin "1") (pinfunction "K_1") (pintype "unspecified"))
      (node (ref "H4") (pin "2") (pinfunction "2_2") (pintype "unspecified"))
      (node (ref "H5") (pin "2") (pinfunction "2_2") (pintype "unspecified"))
      (node (ref "L1") (pin "2") (pinfunction "2_2") (pintype "unspecified"))
      (node (ref "R10") (pin "2") (pinfunction "2_2") (pintype "unspecified"))
      (node (ref "R11") (pin "2") (pinfunction "2_2") (pintype "unspecified"))
      (node (ref "R13") (pin "1") (pinfunction "1_1") (pintype "unspecified"))
      (node (ref "R3") (pin "2") (pinfunction "2_2") (pintype "unspecified"))
      (node (ref "R39") (pin "1") (pinfunction "1_1") (pintype "unspecified"))
      (node (ref "R4") (pin "2") (pinfunction "2_2") (pintype "unspecified"))
      (node (ref "R48") (pin "2") (pinfunction "2_2") (pintype "unspecified"))
      (node (ref "R49") (pin "2") (pinfunction "2_2") (pintype "unspecified"))
      (node (ref "R50") (pin "2") (pinfunction "2_2") (pintype "unspecified"))
      (node (ref "R51") (pin "2") (pinfunction "2_2") (pintype "unspecified"))
      (node (ref "R52") (pin "2") (pinfunction "2_2") (pintype "unspecified"))
      (node (ref "R53") (pin "2") (pinfunction "2_2") (pintype "unspecified"))
      (node (ref "R54") (pin "2") (pinfunction "2_2") (pintype "unspecified"))
      (node (ref "R55") (pin "2") (pinfunction "2_2") (pintype "unspecified"))
      (node (ref "R6") (pin "2") (pinfunction "2_2") (pintype "unspecified"))
      (node (ref "R7") (pin "2") (pinfunction "2_2") (pintype "unspecified"))
      (node (ref "R8") (pin "2") (pinfunction "2_2") (pintype "unspecified"))
      (node (ref "R9") (pin "2") (pinfunction "2_2") (pintype "unspecified"))
      (node (ref "RN1") (pin "1") (pinfunction "1_1") (pintype "unspecified"))
      (node (ref "SW1") (pin "9") (pinfunction "PIN9_9") (pintype "unspecified"))
      (node (ref "SW10") (pin "1") (pinfunction "PIN1_1") (pintype "unspecified"))
      (node (ref "SW2") (pin "10") (pinfunction "PIN10_10") (pintype "unspecified"))
      (node (ref "SW2") (pin "9") (pinfunction "PIN9_9") (pintype "unspecified"))
      (node (ref "SW34") (pin "6") (pinfunction "PIN6_6") (pintype "unspecified"))
      (node (ref "SW35") (pin "5") (pinfunction "A5_5") (pintype "input"))
      (node (ref "SW4") (pin "1") (pinfunction "PIN1_1") (pintype "unspecified"))
      (node (ref "SW6") (pin "11") (pinfunction "PIN11_11") (pintype "unspecified"))
      (node (ref "SW7") (pin "2") (pinfunction "PIN2_2") (pintype "unspecified"))
      (node (ref "SW8") (pin "10") (pinfunction "PIN10_10") (pintype "unspecified"))
      (node (ref "SW9") (pin "1") (pinfunction "PIN1_1") (pintype "unspecified"))
      (node (ref "U1") (pin "27") (pinfunction "5V_27") (pintype "unspecified"))
      (node (ref "U17") (pin "1") (pinfunction "1_1") (pintype "input"))
      (node (ref "U23") (pin "2") (pinfunction "2_2") (pintype "unspecified"))
      (node (ref "U29") (pin "10") (pinfunction "COM_10") (pintype "unspecified"))
      (node (ref "U39") (pin "4") (pinfunction "B3_4") (pintype "input"))
      (node (ref "U41") (pin "4") (pinfunction "B3_4") (pintype "input"))
      (node (ref "U42") (pin "1") (pinfunction "1_1") (pintype "unspecified"))
      (node (ref "U43") (pin "1") (pinfunction "1_1") (pintype "unspecified"))
      (node (ref "U44") (pin "1") (pinfunction "1_1") (pintype "unspecified"))
      (node (ref "U45") (pin "1") (pinfunction "1_1") (pintype "unspecified"))
      (node (ref "U9") (pin "1") (pinfunction "1_1") (pintype "input"))
    )
    (net (code "2") (name "/+5v") (class "Default")
      (node (ref "R12") (pin "1") (pinfunction "1_1") (pintype "unspecified"))
      (node (ref "R2") (pin "2") (pinfunction "2_2") (pintype "input"))
      (node (ref "R2") (pin "3") (pinfunction "3_3") (pintype "input"))
      (node (ref "SW5") (pin "5") (pinfunction "PIN5_5") (pintype "unspecified"))
    )
    (net (code "3") (name "/3V3") (class "Default")
      (node (ref "H5") (pin "1") (pinfunction "1_1") (pintype "unspecified"))
      (node (ref "U1") (pin "17") (pinfunction "3V3_17") (pintype "unspecified"))
    )
    (net (code "4") (name "/7SEG_CLOCK") (class "Default")
      (node (ref "SW10") (pin "5") (pinfunction "PIN5_5") (pintype "unspecified"))
      (node (ref "U21") (pin "11") (pinfunction "SCK_11") (pintype "unspecified"))
    )
    (net (code "5") (name "/7SEG_DIN") (class "Default")
      (node (ref "SW10") (pin "7") (pinfunction "PIN7_7") (pintype "unspecified"))
      (node (ref "U21") (pin "14") (pinfunction "SER_14") (pintype "unspecified"))
    )
    (net (code "6") (name "/7SEG_LATCH") (class "Default")
      (node (ref "SW10") (pin "6") (pinfunction "PIN6_6") (pintype "unspecified"))
      (node (ref "U21") (pin "12") (pinfunction "RCK_12") (pintype "unspecified"))
    )
    (net (code "7") (name "/A0") (class "Default")
      (node (ref "H3") (pin "8") (pinfunction "8_8") (pintype "unspecified"))
      (node (ref "SW11") (pin "9") (pinfunction "9_9") (pintype "input"))
      (node (ref "SW3") (pin "8") (pinfunction "A8_8") (pintype "input"))
      (node (ref "U1") (pin "19") (pinfunction "A0_19") (pintype "unspecified"))
      (node (ref "U28") (pin "8") (pinfunction "8B_8") (pintype "unspecified"))
      (node (ref "U39") (pin "3") (pinfunction "A3_3") (pintype "input"))
    )
    (net (code "8") (name "/A1") (class "Default")
      (node (ref "H3") (pin "7") (pinfunction "7_7") (pintype "unspecified"))
      (node (ref "SW11") (pin "10") (pinfunction "10_10") (pintype "input"))
      (node (ref "SW3") (pin "7") (pinfunction "A7_7") (pintype "input"))
      (node (ref "U1") (pin "20") (pinfunction "A1_20") (pintype "unspecified"))
      (node (ref "U28") (pin "7") (pinfunction "7B_7") (pintype "unspecified"))
    )
    (net (code "9") (name "/A1A") (class "Default")
      (node (ref "R47") (pin "1") (pinfunction "1_1") (pintype "input"))
      (node (ref "U21") (pin "15") (pinfunction "QA_15") (pintype "unspecified"))
    )
    (net (code "10") (name "/A2") (class "Default")
      (node (ref "H3") (pin "6") (pinfunction "6_6") (pintype "unspecified"))
      (node (ref "SW11") (pin "11") (pinfunction "11_11") (pintype "input"))
      (node (ref "SW22") (pin "8") (pinfunction "PIN8_8") (pintype "unspecified"))
      (node (ref "SW3") (pin "6") (pinfunction "A6_6") (pintype "input"))
      (node (ref "U1") (pin "21") (pinfunction "A2_21") (pintype "unspecified"))
      (node (ref "U28") (pin "6") (pinfunction "6B_6") (pintype "unspecified"))
    )
    (net (code "11") (name "/A3") (class "Default")
      (node (ref "H3") (pin "5") (pinfunction "5_5") (pintype "unspecified"))
      (node (ref "SW11") (pin "12") (pinfunction "12_12") (pintype "input"))
      (node (ref "SW22") (pin "7") (pinfunction "PIN7_7") (pintype "unspecified"))
      (node (ref "SW3") (pin "5") (pinfunction "A5_5") (pintype "input"))
      (node (ref "U1") (pin "22") (pinfunction "A3_22") (pintype "unspecified"))
      (node (ref "U28") (pin "5") (pinfunction "5B_5") (pintype "unspecified"))
    )
    (net (code "12") (name "/A4") (class "Default")
      (node (ref "H3") (pin "4") (pinfunction "4_4") (pintype "unspecified"))
      (node (ref "R4") (pin "1") (pinfunction "1_1") (pintype "unspecified"))
      (node (ref "SW11") (pin "13") (pinfunction "13_13") (pintype "input"))
      (node (ref "SW2") (pin "7") (pinfunction "PIN7_7") (pintype "unspecified"))
      (node (ref "SW3") (pin "4") (pinfunction "A4_4") (pintype "input"))
      (node (ref "SW34") (pin "8") (pinfunction "PIN8_8") (pintype "unspecified"))
      (node (ref "SW4") (pin "4") (pinfunction "PIN4_4") (pintype "unspecified"))
      (node (ref "SW7") (pin "3") (pinfunction "PIN3_3") (pintype "unspecified"))
      (node (ref "U1") (pin "23") (pinfunction "SDA/A4_23") (pintype "unspecified"))
      (node (ref "U28") (pin "4") (pinfunction "4B_4") (pintype "unspecified"))
    )
    (net (code "13") (name "/A5") (class "Default")
      (node (ref "H3") (pin "3") (pinfunction "3_3") (pintype "unspecified"))
      (node (ref "R3") (pin "1") (pinfunction "1_1") (pintype "unspecified"))
      (node (ref "SW11") (pin "14") (pinfunction "14_14") (pintype "input"))
      (node (ref "SW2") (pin "8") (pinfunction "PIN8_8") (pintype "unspecified"))
      (node (ref "SW3") (pin "3") (pinfunction "A3_3") (pintype "input"))
      (node (ref "SW34") (pin "7") (pinfunction "PIN7_7") (pintype "unspecified"))
      (node (ref "SW4") (pin "3") (pinfunction "PIN3_3") (pintype "unspecified"))
      (node (ref "SW7") (pin "4") (pinfunction "PIN4_4") (pintype "unspecified"))
      (node (ref "U1") (pin "24") (pinfunction "SCL/A5_24") (pintype "unspecified"))
      (node (ref "U28") (pin "3") (pinfunction "3B_3") (pintype "unspecified"))
    )
    (net (code "14") (name "/A6") (class "Default")
      (node (ref "H3") (pin "2") (pinfunction "2_2") (pintype "unspecified"))
      (node (ref "SW11") (pin "15") (pinfunction "15_15") (pintype "input"))
      (node (ref "SW22") (pin "6") (pinfunction "PIN6_6") (pintype "unspecified"))
      (node (ref "SW3") (pin "2") (pinfunction "A2_2") (pintype "input"))
      (node (ref "U1") (pin "25") (pinfunction "A6_25") (pintype "unspecified"))
      (node (ref "U28") (pin "2") (pinfunction "2B_2") (pintype "unspecified"))
    )
    (net (code "15") (name "/A7") (class "Default")
      (node (ref "H3") (pin "1") (pinfunction "1_1") (pintype "unspecified"))
      (node (ref "SW11") (pin "16") (pinfunction "16_16") (pintype "input"))
      (node (ref "SW22") (pin "5") (pinfunction "PIN5_5") (pintype "unspecified"))
      (node (ref "SW3") (pin "1") (pinfunction "A1_1") (pintype "input"))
      (node (ref "U1") (pin "26") (pinfunction "A7_26") (pintype "unspecified"))
      (node (ref "U28") (pin "1") (pinfunction "1B_1") (pintype "unspecified"))
    )
    (net (code "16") (name "/ACLOCK") (class "Default")
      (node (ref "SW9") (pin "5") (pinfunction "PIN5_5") (pintype "unspecified"))
      (node (ref "U25") (pin "11") (pinfunction "SCK_11") (pintype "unspecified"))
      (node (ref "U26") (pin "11") (pinfunction "SCK_11") (pintype "unspecified"))
    )
    (net (code "17") (name "/ADIN") (class "Default")
      (node (ref "SW9") (pin "7") (pinfunction "PIN7_7") (pintype "unspecified"))
      (node (ref "U26") (pin "14") (pinfunction "SER_14") (pintype "unspecified"))
    )
    (net (code "18") (name "/ALATCH") (class "Default")
      (node (ref "SW9") (pin "6") (pinfunction "PIN6_6") (pintype "unspecified"))
      (node (ref "U25") (pin "12") (pinfunction "RCK_12") (pintype "unspecified"))
      (node (ref "U26") (pin "12") (pinfunction "RCK_12") (pintype "unspecified"))
    )
    (net (code "19") (name "/AREF") (class "Default")
      (node (ref "C6") (pin "2") (pinfunction "2_2") (pintype "unspecified"))
      (node (ref "R39") (pin "2") (pinfunction "2_2") (pintype "unspecified"))
      (node (ref "U1") (pin "18") (pinfunction "AREF_18") (pintype "unspecified"))
    )
    (net (code "20") (name "/B1") (class "Default")
      (node (ref "R46") (pin "1") (pinfunction "1_1") (pintype "input"))
      (node (ref "U21") (pin "1") (pinfunction "QB_1") (pintype "unspecified"))
    )
    (net (code "21") (name "/BC1") (class "Default")
      (node (ref "Q1") (pin "1") (pinfunction "G_1") (pintype "unspecified"))
      (node (ref "R22") (pin "2") (pinfunction "2_2") (pintype "unspecified"))
      (node (ref "SW33") (pin "9") (pinfunction "9_9") (pintype "input"))
      (node (ref "SW9") (pin "2") (pinfunction "PIN2_2") (pintype "unspecified"))
      (node (ref "U1") (pin "7") (pinfunction "D4_7") (pintype "unspecified"))
    )
    (net (code "22") (name "/BC2") (class "Default")
      (node (ref "Q4") (pin "1") (pinfunction "G_1") (pintype "unspecified"))
      (node (ref "R19") (pin "2") (pinfunction "2_2") (pintype "unspecified"))
      (node (ref "SW33") (pin "10") (pinfunction "10_10") (pintype "input"))
      (node (ref "SW6") (pin "9") (pinfunction "PIN9_9") (pintype "unspecified"))
      (node (ref "SW8") (pin "7") (pinfunction "PIN7_7") (pintype "unspecified"))
      (node (ref "U1") (pin "10") (pinfunction "D7_10") (pintype "unspecified"))
    )
    (net (code "23") (name "/BC3") (class "Default")
      (node (ref "SW33") (pin "11") (pinfunction "11_11") (pintype "input"))
      (node (ref "SW6") (pin "10") (pinfunction "PIN10_10") (pintype "unspecified"))
      (node (ref "SW8") (pin "6") (pinfunction "PIN6_6") (pintype "unspecified"))
      (node (ref "U1") (pin "11") (pinfunction "D8_11") (pintype "unspecified"))
      (node (ref "U41") (pin "3") (pinfunction "A3_3") (pintype "input"))
    )
    (net (code "24") (name "/BC4") (class "Default")
      (node (ref "SW10") (pin "2") (pinfunction "PIN2_2") (pintype "unspecified"))
      (node (ref "SW33") (pin "12") (pinfunction "12_12") (pintype "input"))
      (node (ref "SW35") (pin "4") (pinfunction "A4_4") (pintype "input"))
      (node (ref "U1") (pin "12") (pinfunction "D9_12") (pintype "unspecified"))
    )
    (net (code "25") (name "/BR1") (class "Default")
      (node (ref "SW1") (pin "10") (pinfunction "PIN10_10") (pintype "unspecified"))
      (node (ref "SW33") (pin "16") (pinfunction "16_16") (pintype "input"))
      (node (ref "SW9") (pin "4") (pinfunction "PIN4_4") (pintype "unspecified"))
      (node (ref "U1") (pin "16") (pinfunction "SCK/D13_16") (pintype "unspecified"))
      (node (ref "U23") (pin "4") (pinfunction "4_4") (pintype "unspecified"))
    )
    (net (code "26") (name "/BR2") (class "Default")
      (node (ref "SW33") (pin "15") (pinfunction "15_15") (pintype "input"))
      (node (ref "SW9") (pin "3") (pinfunction "PIN3_3") (pintype "unspecified"))
      (node (ref "U1") (pin "15") (pinfunction "D12/MISO_15") (pintype "unspecified"))
      (node (ref "U23") (pin "6") (pinfunction "6_6") (pintype "unspecified"))
    )
    (net (code "27") (name "/BR3") (class "Default")
      (node (ref "SW10") (pin "4") (pinfunction "PIN4_4") (pintype "unspecified"))
      (node (ref "SW33") (pin "14") (pinfunction "14_14") (pintype "input"))
      (node (ref "SW6") (pin "13") (pinfunction "PIN13_13") (pintype "unspecified"))
      (node (ref "U1") (pin "14") (pinfunction "D11/MOSI_14") (pintype "unspecified"))
      (node (ref "U23") (pin "5") (pinfunction "5_5") (pintype "unspecified"))
    )
    (net (code "28") (name "/BR4") (class "Default")
      (node (ref "SW10") (pin "3") (pinfunction "PIN3_3") (pintype "unspecified"))
      (node (ref "SW33") (pin "13") (pinfunction "13_13") (pintype "input"))
      (node (ref "SW6") (pin "12") (pinfunction "PIN12_12") (pintype "unspecified"))
      (node (ref "U1") (pin "13") (pinfunction "D10/SS_13") (pintype "unspecified"))
      (node (ref "U23") (pin "7") (pinfunction "7_7") (pintype "unspecified"))
    )
    (net (code "29") (name "/C1") (class "Default")
      (node (ref "R38") (pin "2") (pinfunction "2_2") (pintype "input"))
      (node (ref "U26") (pin "15") (pinfunction "QA_15") (pintype "unspecified"))
    )
    (net (code "30") (name "/C1A") (class "Default")
      (node (ref "R45") (pin "1") (pinfunction "1_1") (pintype "input"))
      (node (ref "U21") (pin "2") (pinfunction "QC_2") (pintype "unspecified"))
    )
    (net (code "31") (name "/C2") (class "Default")
      (node (ref "R37") (pin "2") (pinfunction "2_2") (pintype "input"))
      (node (ref "U26") (pin "1") (pinfunction "QB_1") (pintype "unspecified"))
    )
    (net (code "32") (name "/C3") (class "Default")
      (node (ref "R36") (pin "2") (pinfunction "2_2") (pintype "input"))
      (node (ref "U26") (pin "2") (pinfunction "QC_2") (pintype "unspecified"))
    )
    (net (code "33") (name "/C4") (class "Default")
      (node (ref "R35") (pin "2") (pinfunction "2_2") (pintype "input"))
      (node (ref "U26") (pin "3") (pinfunction "QD_3") (pintype "unspecified"))
    )
    (net (code "34") (name "/C5") (class "Default")
      (node (ref "R34") (pin "2") (pinfunction "2_2") (pintype "input"))
      (node (ref "U26") (pin "4") (pinfunction "QE_4") (pintype "unspecified"))
    )
    (net (code "35") (name "/C6") (class "Default")
      (node (ref "R33") (pin "2") (pinfunction "2_2") (pintype "input"))
      (node (ref "U26") (pin "5") (pinfunction "QF_5") (pintype "unspecified"))
    )
    (net (code "36") (name "/C7") (class "Default")
      (node (ref "R32") (pin "2") (pinfunction "2_2") (pintype "input"))
      (node (ref "U26") (pin "6") (pinfunction "QG_6") (pintype "unspecified"))
    )
    (net (code "37") (name "/C8") (class "Default")
      (node (ref "R31") (pin "2") (pinfunction "2_2") (pintype "input"))
      (node (ref "U26") (pin "7") (pinfunction "QH_7") (pintype "unspecified"))
    )
    (net (code "38") (name "/C9") (class "Default")
      (node (ref "R27") (pin "2") (pinfunction "2_2") (pintype "input"))
      (node (ref "U25") (pin "15") (pinfunction "QA_15") (pintype "unspecified"))
    )
    (net (code "39") (name "/C10") (class "Default")
      (node (ref "R26") (pin "2") (pinfunction "2_2") (pintype "input"))
      (node (ref "U25") (pin "1") (pinfunction "QB_1") (pintype "unspecified"))
    )
    (net (code "40") (name "/C11") (class "Default")
      (node (ref "R25") (pin "2") (pinfunction "2_2") (pintype "input"))
      (node (ref "U25") (pin "2") (pinfunction "QC_2") (pintype "unspecified"))
    )
    (net (code "41") (name "/C12") (class "Default")
      (node (ref "R24") (pin "2") (pinfunction "2_2") (pintype "input"))
      (node (ref "U25") (pin "3") (pinfunction "QD_3") (pintype "unspecified"))
    )
    (net (code "42") (name "/C13") (class "Default")
      (node (ref "R23") (pin "2") (pinfunction "2_2") (pintype "input"))
      (node (ref "U25") (pin "4") (pinfunction "QE_4") (pintype "unspecified"))
    )
    (net (code "43") (name "/C14") (class "Default")
      (node (ref "R28") (pin "2") (pinfunction "2_2") (pintype "input"))
      (node (ref "U25") (pin "5") (pinfunction "QF_5") (pintype "unspecified"))
    )
    (net (code "44") (name "/C15") (class "Default")
      (node (ref "R29") (pin "2") (pinfunction "2_2") (pintype "input"))
      (node (ref "U25") (pin "6") (pinfunction "QG_6") (pintype "unspecified"))
    )
    (net (code "45") (name "/C16") (class "Default")
      (node (ref "R30") (pin "2") (pinfunction "2_2") (pintype "input"))
      (node (ref "U25") (pin "7") (pinfunction "QH_7") (pintype "unspecified"))
    )
    (net (code "46") (name "/D1") (class "Default")
      (node (ref "R44") (pin "1") (pinfunction "1_1") (pintype "input"))
      (node (ref "U21") (pin "3") (pinfunction "QD_3") (pintype "unspecified"))
    )
    (net (code "47") (name "/DP1") (class "Default")
      (node (ref "R40") (pin "1") (pinfunction "1_1") (pintype "input"))
      (node (ref "U21") (pin "7") (pinfunction "QH_7") (pintype "unspecified"))
    )
    (net (code "48") (name "/E1") (class "Default")
      (node (ref "R43") (pin "1") (pinfunction "1_1") (pintype "input"))
      (node (ref "U21") (pin "4") (pinfunction "QE_4") (pintype "unspecified"))
    )
    (net (code "49") (name "/ENA") (class "Default")
      (node (ref "U10") (pin "2") (pinfunction "2_2") (pintype "unspecified"))
      (node (ref "U8") (pin "8") (pinfunction "ENABLE_A_8") (pintype "unspecified"))
    )
    (net (code "50") (name "/ENA_L298") (class "Default")
      (node (ref "Q2") (pin "1") (pinfunction "G_1") (pintype "unspecified"))
      (node (ref "R21") (pin "2") (pinfunction "2_2") (pintype "unspecified"))
      (node (ref "SW6") (pin "8") (pinfunction "PIN8_8") (pintype "unspecified"))
      (node (ref "SW8") (pin "9") (pinfunction "PIN9_9") (pintype "unspecified"))
      (node (ref "U1") (pin "8") (pinfunction "D5_8") (pintype "unspecified"))
    )
    (net (code "51") (name "/ENB") (class "Default")
      (node (ref "U18") (pin "2") (pinfunction "2_2") (pintype "unspecified"))
      (node (ref "U8") (pin "14") (pinfunction "ENABLE_B_14") (pintype "unspecified"))
    )
    (net (code "52") (name "/ENB_L298") (class "Default")
      (node (ref "Q3") (pin "1") (pinfunction "G_1") (pintype "unspecified"))
      (node (ref "R20") (pin "2") (pinfunction "2_2") (pintype "unspecified"))
      (node (ref "SW6") (pin "14") (pinfunction "PIN14_14") (pintype "unspecified"))
      (node (ref "SW8") (pin "8") (pinfunction "PIN8_8") (pintype "unspecified"))
      (node (ref "U1") (pin "9") (pinfunction "D6_9") (pintype "unspecified"))
    )
    (net (code "53") (name "/ENCO_1") (class "Default")
      (node (ref "SW1") (pin "6") (pinfunction "PIN6_6") (pintype "unspecified"))
      (node (ref "SW5") (pin "6") (pinfunction "PIN6_6") (pintype "unspecified"))
      (node (ref "U1") (pin "5") (pinfunction "D2/INT0_5") (pintype "unspecified"))
    )
    (net (code "54") (name "/ENCO_2") (class "Default")
      (node (ref "SW1") (pin "7") (pinfunction "PIN7_7") (pintype "unspecified"))
      (node (ref "SW5") (pin "7") (pinfunction "PIN7_7") (pintype "unspecified"))
      (node (ref "U1") (pin "6") (pinfunction "D3/INT1_6") (pintype "unspecified"))
    )
    (net (code "55") (name "/F1") (class "Default")
      (node (ref "R42") (pin "1") (pinfunction "1_1") (pintype "input"))
      (node (ref "U21") (pin "5") (pinfunction "QF_5") (pintype "unspecified"))
    )
    (net (code "56") (name "/FB") (class "Default")
      (node (ref "R1") (pin "2") (pinfunction "2_2") (pintype "unspecified"))
      (node (ref "R12") (pin "2") (pinfunction "2_2") (pintype "unspecified"))
      (node (ref "R2") (pin "1") (pinfunction "1_1") (pintype "input"))
      (node (ref "U7") (pin "4") (pinfunction "FB_4") (pintype "unspecified"))
    )
    (net (code "57") (name "/G1") (class "Default")
      (node (ref "R41") (pin "1") (pinfunction "1_1") (pintype "input"))
      (node (ref "U21") (pin "6") (pinfunction "QG_6") (pintype "unspecified"))
    )
    (net (code "58") (name "/H1") (class "Default")
      (node (ref "U24") (pin "9") (pinfunction "R1_9") (pintype "unspecified"))
      (node (ref "U27") (pin "9") (pinfunction "R1_9") (pintype "unspecified"))
      (node (ref "U28") (pin "18") (pinfunction "1C_18") (pintype "unspecified"))
    )
    (net (code "59") (name "/H2") (class "Default")
      (node (ref "U24") (pin "14") (pinfunction "R2_14") (pintype "unspecified"))
      (node (ref "U27") (pin "14") (pinfunction "R2_14") (pintype "unspecified"))
      (node (ref "U28") (pin "17") (pinfunction "2C_17") (pintype "unspecified"))
    )
    (net (code "60") (name "/H3") (class "Default")
      (node (ref "U24") (pin "8") (pinfunction "R3_8") (pintype "unspecified"))
      (node (ref "U27") (pin "8") (pinfunction "R3_8") (pintype "unspecified"))
      (node (ref "U28") (pin "16") (pinfunction "3C_16") (pintype "unspecified"))
    )
    (net (code "61") (name "/H4") (class "Default")
      (node (ref "U24") (pin "12") (pinfunction "R4_12") (pintype "unspecified"))
      (node (ref "U27") (pin "12") (pinfunction "R4_12") (pintype "unspecified"))
      (node (ref "U28") (pin "15") (pinfunction "4C_15") (pintype "unspecified"))
    )
    (net (code "62") (name "/H5") (class "Default")
      (node (ref "U24") (pin "1") (pinfunction "R5_1") (pintype "unspecified"))
      (node (ref "U27") (pin "1") (pinfunction "R5_1") (pintype "unspecified"))
      (node (ref "U28") (pin "14") (pinfunction "5C_14") (pintype "unspecified"))
    )
    (net (code "63") (name "/H6") (class "Default")
      (node (ref "U24") (pin "7") (pinfunction "R6_7") (pintype "unspecified"))
      (node (ref "U27") (pin "7") (pinfunction "R6_7") (pintype "unspecified"))
      (node (ref "U28") (pin "13") (pinfunction "6C_13") (pintype "unspecified"))
    )
    (net (code "64") (name "/H7") (class "Default")
      (node (ref "U24") (pin "2") (pinfunction "R7_2") (pintype "unspecified"))
      (node (ref "U27") (pin "2") (pinfunction "R7_2") (pintype "unspecified"))
      (node (ref "U28") (pin "12") (pinfunction "7C_12") (pintype "unspecified"))
    )
    (net (code "65") (name "/H8") (class "Default")
      (node (ref "U24") (pin "5") (pinfunction "R8_5") (pintype "unspecified"))
      (node (ref "U27") (pin "5") (pinfunction "R8_5") (pintype "unspecified"))
      (node (ref "U28") (pin "11") (pinfunction "8C_11") (pintype "unspecified"))
    )
    (net (code "66") (name "/IN1_L298") (class "Default")
      (node (ref "SW6") (pin "2") (pinfunction "PIN2_2") (pintype "unspecified"))
      (node (ref "U8") (pin "7") (pinfunction "INPUT_1_7") (pintype "unspecified"))
    )
    (net (code "67") (name "/IN2_L298") (class "Default")
      (node (ref "SW6") (pin "3") (pinfunction "PIN3_3") (pintype "unspecified"))
      (node (ref "U8") (pin "9") (pinfunction "INPUT_2_9") (pintype "unspecified"))
    )
    (net (code "68") (name "/IN3_L298") (class "Default")
      (node (ref "SW6") (pin "5") (pinfunction "PIN5_5") (pintype "unspecified"))
      (node (ref "U8") (pin "13") (pinfunction "INPUT_3_13") (pintype "unspecified"))
    )
    (net (code "69") (name "/IN4_L298") (class "Default")
      (node (ref "SW6") (pin "6") (pinfunction "PIN6_6") (pintype "unspecified"))
      (node (ref "U8") (pin "15") (pinfunction "INPUT_4_15") (pintype "unspecified"))
    )
    (net (code "70") (name "/OUT1") (class "Default")
      (node (ref "U25") (pin "14") (pinfunction "SER_14") (pintype "unspecified"))
      (node (ref "U26") (pin "9") (pinfunction "QH'_9") (pintype "unspecified"))
    )
    (net (code "71") (name "/OUT1M") (class "Default")
      (node (ref "D2") (pin "2") (pinfunction "A_2") (pintype "unspecified"))
      (node (ref "D4") (pin "1") (pinfunction "K_1") (pintype "unspecified"))
      (node (ref "U14") (pin "1") (pinfunction "1_1") (pintype "unspecified"))
      (node (ref "U8") (pin "4") (pinfunction "OUT_1_4") (pintype "unspecified"))
    )
    (net (code "72") (name "/OUT2M") (class "Default")
      (node (ref "D3") (pin "2") (pinfunction "A_2") (pintype "unspecified"))
      (node (ref "D5") (pin "1") (pinfunction "K_1") (pintype "unspecified"))
      (node (ref "U14") (pin "2") (pinfunction "2_2") (pintype "unspecified"))
      (node (ref "U8") (pin "5") (pinfunction "OUT_2_5") (pintype "unspecified"))
    )
    (net (code "73") (name "/OUT3M") (class "Default")
      (node (ref "D6") (pin "1") (pinfunction "K_1") (pintype "unspecified"))
      (node (ref "D8") (pin "2") (pinfunction "A_2") (pintype "unspecified"))
      (node (ref "U13") (pin "2") (pinfunction "2_2") (pintype "unspecified"))
      (node (ref "U8") (pin "16") (pinfunction "OUT_3_16") (pintype "unspecified"))
    )
    (net (code "74") (name "/OUT4M") (class "Default")
      (node (ref "D7") (pin "1") (pinfunction "K_1") (pintype "unspecified"))
      (node (ref "D9") (pin "2") (pinfunction "A_2") (pintype "unspecified"))
      (node (ref "U13") (pin "1") (pinfunction "1_1") (pintype "unspecified"))
      (node (ref "U8") (pin "17") (pinfunction "OUT_4_17") (pintype "unspecified"))
    )
    (net (code "75") (name "/RST") (class "Default")
      (node (ref "U1") (pin "3") (pinfunction "RST_3") (pintype "unspecified"))
      (node (ref "U23") (pin "3") (pinfunction "3_3") (pintype "unspecified"))
    )
    (net (code "76") (name "/RX") (class "Default")
      (node (ref "H4") (pin "4") (pinfunction "4_4") (pintype "unspecified"))
      (node (ref "U1") (pin "2") (pinfunction "RX_2") (pintype "unspecified"))
    )
    (net (code "77") (name "/TX") (class "Default")
      (node (ref "H4") (pin "3") (pinfunction "3_3") (pintype "unspecified"))
      (node (ref "U1") (pin "1") (pinfunction "TX_1") (pintype "unspecified"))
    )
    (net (code "78") (name "/ULN_VDD") (class "Default")
      (node (ref "C5") (pin "1") (pinfunction "1_1") (pintype "unspecified"))
      (node (ref "CN1") (pin "5") (pinfunction "5_5") (pintype "unspecified"))
      (node (ref "R15") (pin "1") (pinfunction "1_1") (pintype "unspecified"))
      (node (ref "R16") (pin "1") (pinfunction "1_1") (pintype "unspecified"))
      (node (ref "R17") (pin "1") (pinfunction "1_1") (pintype "unspecified"))
      (node (ref "R18") (pin "1") (pinfunction "1_1") (pintype "unspecified"))
      (node (ref "SW8") (pin "1") (pinfunction "PIN1_1") (pintype "unspecified"))
      (node (ref "U19") (pin "10") (pinfunction "COM_10") (pintype "unspecified"))
    )
    (net (code "79") (name "/VLED") (class "Default")
      (node (ref "SW9") (pin "8") (pinfunction "PIN8_8") (pintype "unspecified"))
      (node (ref "U25") (pin "10") (pinfunction "SCLR#_10") (pintype "unspecified"))
      (node (ref "U25") (pin "16") (pinfunction "VCC_16") (pintype "unspecified"))
      (node (ref "U26") (pin "10") (pinfunction "SCLR#_10") (pintype "unspecified"))
      (node (ref "U26") (pin "16") (pinfunction "VCC_16") (pintype "unspecified"))
      (node (ref "U28") (pin "10") (pinfunction "COM_10") (pintype "unspecified"))
    )
    (net (code "80") (name "/VS") (class "Default")
      (node (ref "SW6") (pin "4") (pinfunction "PIN4_4") (pintype "unspecified"))
      (node (ref "U10") (pin "1") (pinfunction "1_1") (pintype "unspecified"))
      (node (ref "U18") (pin "1") (pinfunction "1_1") (pintype "unspecified"))
      (node (ref "U8") (pin "6") (pinfunction "VS_6") (pintype "unspecified"))
    )
    (net (code "81") (name "/Vs") (class "Default")
      (node (ref "R14") (pin "2") (pinfunction "2_2") (pintype "unspecified"))
    )
    (net (code "82") (name "7SEG_VDD") (class "Default")
      (node (ref "Q1") (pin "3") (pinfunction "D_3") (pintype "unspecified"))
      (node (ref "Q2") (pin "3") (pinfunction "D_3") (pintype "unspecified"))
      (node (ref "Q3") (pin "3") (pinfunction "D_3") (pintype "unspecified"))
      (node (ref "Q4") (pin "3") (pinfunction "D_3") (pintype "unspecified"))
      (node (ref "R19") (pin "1") (pinfunction "1_1") (pintype "unspecified"))
      (node (ref "R20") (pin "1") (pinfunction "1_1") (pintype "unspecified"))
      (node (ref "R21") (pin "1") (pinfunction "1_1") (pintype "unspecified"))
      (node (ref "R22") (pin "1") (pinfunction "1_1") (pintype "unspecified"))
      (node (ref "SW10") (pin "8") (pinfunction "PIN8_8") (pintype "unspecified"))
      (node (ref "U21") (pin "10") (pinfunction "SCLR#_10") (pintype "unspecified"))
      (node (ref "U21") (pin "16") (pinfunction "VCC_16") (pintype "unspecified"))
    )
    (net (code "83") (name "GND") (class "Default")
      (node (ref "C1") (pin "2") (pinfunction "2_2") (pintype "unspecified"))
      (node (ref "C2") (pin "1") (pinfunction "1_1") (pintype "unspecified"))
      (node (ref "C3") (pin "1") (pinfunction "1_1") (pintype "unspecified"))
      (node (ref "C4") (pin "1") (pinfunction "1_1") (pintype "unspecified"))
      (node (ref "C5") (pin "2") (pinfunction "2_2") (pintype "unspecified"))
      (node (ref "C6") (pin "1") (pinfunction "1_1") (pintype "unspecified"))
      (node (ref "C7") (pin "2") (pinfunction "2_2") (pintype "unspecified"))
      (node (ref "D1") (pin "2") (pinfunction "A_2") (pintype "unspecified"))
      (node (ref "D4") (pin "2") (pinfunction "A_2") (pintype "unspecified"))
      (node (ref "D5") (pin "2") (pinfunction "A_2") (pintype "unspecified"))
      (node (ref "D6") (pin "2") (pinfunction "A_2") (pintype "unspecified"))
      (node (ref "D7") (pin "2") (pinfunction "A_2") (pintype "unspecified"))
      (node (ref "H4") (pin "1") (pinfunction "1_1") (pintype "unspecified"))
      (node (ref "H5") (pin "3") (pinfunction "3_3") (pintype "unspecified"))
      (node (ref "H5") (pin "4") (pinfunction "4_4") (pintype "unspecified"))
      (node (ref "LED1") (pin "2") (pinfunction "K_2") (pintype "unspecified"))
      (node (ref "LED2") (pin "2") (pinfunction "K_2") (pintype "unspecified"))
      (node (ref "R1") (pin "1") (pinfunction "1_1") (pintype "unspecified"))
      (node (ref "SW1") (pin "8") (pinfunction "PIN8_8") (pintype "unspecified"))
      (node (ref "SW12") (pin "4") (pinfunction "4_4") (pintype "unspecified"))
      (node (ref "SW13") (pin "4") (pinfunction "4_4") (pintype "unspecified"))
      (node (ref "SW14") (pin "4") (pinfunction "4_4") (pintype "unspecified"))
      (node (ref "SW15") (pin "4") (pinfunction "4_4") (pintype "unspecified"))
      (node (ref "SW2") (pin "6") (pinfunction "PIN6_6") (pintype "unspecified"))
      (node (ref "SW34") (pin "5") (pinfunction "PIN5_5") (pintype "unspecified"))
      (node (ref "SW35") (pin "6") (pinfunction "A6_6") (pintype "input"))
      (node (ref "SW4") (pin "2") (pinfunction "PIN2_2") (pintype "unspecified"))
      (node (ref "SW5") (pin "8") (pinfunction "PIN8_8") (pintype "unspecified"))
      (node (ref "SW7") (pin "1") (pinfunction "PIN1_1") (pintype "unspecified"))
      (node (ref "U1") (pin "29") (pinfunction "GND_29") (pintype "unspecified"))
      (node (ref "U1") (pin "4") (pinfunction "GND_4") (pintype "unspecified"))
      (node (ref "U11") (pin "2") (pinfunction "2_2") (pintype "unspecified"))
      (node (ref "U11") (pin "3") (pinfunction "3_3") (pintype "unspecified"))
      (node (ref "U12") (pin "2") (pinfunction "2_2") (pintype "unspecified"))
      (node (ref "U16") (pin "2") (pinfunction "2_2") (pintype "unspecified"))
      (node (ref "U17") (pin "2") (pinfunction "2_2") (pintype "input"))
      (node (ref "U19") (pin "9") (pinfunction "E_9") (pintype "unspecified"))
      (node (ref "U21") (pin "13") (pinfunction "G#_13") (pintype "unspecified"))
      (node (ref "U21") (pin "8") (pinfunction "GND_8") (pintype "unspecified"))
      (node (ref "U23") (pin "1") (pinfunction "1_1") (pintype "unspecified"))
      (node (ref "U25") (pin "13") (pinfunction "G#_13") (pintype "unspecified"))
      (node (ref "U25") (pin "8") (pinfunction "GND_8") (pintype "unspecified"))
      (node (ref "U26") (pin "13") (pinfunction "G#_13") (pintype "unspecified"))
      (node (ref "U26") (pin "8") (pinfunction "GND_8") (pintype "unspecified"))
      (node (ref "U28") (pin "9") (pinfunction "E_9") (pintype "unspecified"))
      (node (ref "U29") (pin "9") (pinfunction "E_9") (pintype "unspecified"))
      (node (ref "U38") (pin "3") (pinfunction "GND_3") (pintype "unspecified"))
      (node (ref "U40") (pin "4") (pinfunction "GND_4") (pintype "unspecified"))
      (node (ref "U7") (pin "3") (pinfunction "GND_3") (pintype "unspecified"))
      (node (ref "U7") (pin "5") (pinfunction "ON/OFF_5") (pintype "unspecified"))
      (node (ref "U7") (pin "6") (pinfunction "GND_6") (pintype "unspecified"))
      (node (ref "U8") (pin "1") (pinfunction "GND_1") (pintype "unspecified"))
      (node (ref "U8") (pin "10") (pinfunction "GND_10") (pintype "unspecified"))
      (node (ref "U8") (pin "11") (pinfunction "GND_11") (pintype "unspecified"))
      (node (ref "U8") (pin "19") (pinfunction "SENSE_B_19") (pintype "unspecified"))
      (node (ref "U8") (pin "2") (pinfunction "SENSE_A_2") (pintype "unspecified"))
      (node (ref "U8") (pin "20") (pinfunction "GND_20") (pintype "unspecified"))
      (node (ref "U8") (pin "21") (pinfunction "EP_21") (pintype "unspecified"))
      (node (ref "U9") (pin "2") (pinfunction "2_2") (pintype "input"))
    )
    (net (code "84") (name "GND1307") (class "Default")
      (node (ref "BAT1") (pin "2") (pinfunction "2_2") (pintype "input"))
      (node (ref "SW4") (pin "7") (pinfunction "PIN7_7") (pintype "unspecified"))
      (node (ref "U4") (pin "4") (pinfunction "GND_4") (pintype "passive"))
      (node (ref "U5") (pin "3") (pinfunction "GND_3") (pintype "input"))
    )
    (net (code "85") (name "Net-(IC1-ENABLE)") (class "Default")
      (node (ref "IC1") (pin "6") (pinfunction "ENABLE_6") (pintype "unspecified"))
      (node (ref "SW1") (pin "1") (pinfunction "PIN1_1") (pintype "unspecified"))
    )
    (net (code "86") (name "Net-(IC1-GND)") (class "Default")
      (node (ref "IC1") (pin "4") (pinfunction "GND_4") (pintype "unspecified"))
      (node (ref "SW1") (pin "3") (pinfunction "PIN3_3") (pintype "unspecified"))
    )
    (net (code "87") (name "Net-(IC1-RX)") (class "Default")
      (node (ref "IC1") (pin "2") (pinfunction "RX_2") (pintype "unspecified"))
      (node (ref "SW1") (pin "5") (pinfunction "PIN5_5") (pintype "unspecified"))
    )
    (net (code "88") (name "Net-(IC1-TX)") (class "Default")
      (node (ref "IC1") (pin "3") (pinfunction "TX_3") (pintype "unspecified"))
      (node (ref "SW1") (pin "4") (pinfunction "PIN4_4") (pintype "unspecified"))
    )
    (net (code "89") (name "Net-(IC1-VCC)") (class "Default")
      (node (ref "IC1") (pin "5") (pinfunction "VCC_5") (pintype "unspecified"))
      (node (ref "SW1") (pin "2") (pinfunction "PIN2_2") (pintype "unspecified"))
    )
    (net (code "90") (name "Net-(LCD1-GND)") (class "Default")
      (node (ref "LCD1") (pin "1") (pinfunction "GND_1") (pintype "unspecified"))
      (node (ref "SW7") (pin "8") (pinfunction "PIN8_8") (pintype "unspecified"))
    )
    (net (code "91") (name "Net-(LCD1-SCL)") (class "Default")
      (node (ref "LCD1") (pin "4") (pinfunction "SCL_4") (pintype "unspecified"))
      (node (ref "SW7") (pin "5") (pinfunction "PIN5_5") (pintype "unspecified"))
    )
    (net (code "92") (name "Net-(LCD1-SDA)") (class "Default")
      (node (ref "LCD1") (pin "3") (pinfunction "SDA_3") (pintype "unspecified"))
      (node (ref "SW7") (pin "6") (pinfunction "PIN6_6") (pintype "unspecified"))
    )
    (net (code "93") (name "Net-(LCD1-VCC)") (class "Default")
      (node (ref "LCD1") (pin "2") (pinfunction "VCC_2") (pintype "unspecified"))
      (node (ref "SW7") (pin "7") (pinfunction "PIN7_7") (pintype "unspecified"))
    )
    (net (code "94") (name "Net-(LED1-A)") (class "Default")
      (node (ref "LED1") (pin "1") (pinfunction "A_1") (pintype "unspecified"))
      (node (ref "R13") (pin "2") (pinfunction "2_2") (pintype "unspecified"))
    )
    (net (code "95") (name "Net-(LED2-A)") (class "Default")
      (node (ref "LED2") (pin "1") (pinfunction "A_1") (pintype "unspecified"))
      (node (ref "R14") (pin "1") (pinfunction "1_1") (pintype "unspecified"))
    )
    (net (code "96") (name "Net-(LED3-+)") (class "Default")
      (node (ref "LED3") (pin "1") (pinfunction "+_1") (pintype "unspecified"))
      (node (ref "R15") (pin "2") (pinfunction "2_2") (pintype "unspecified"))
    )
    (net (code "97") (name "Net-(LED3--)") (class "Default")
      (node (ref "CN1") (pin "1") (pinfunction "1_1") (pintype "unspecified"))
      (node (ref "LED3") (pin "2") (pinfunction "-_2") (pintype "unspecified"))
      (node (ref "U19") (pin "18") (pinfunction "1C_18") (pintype "unspecified"))
    )
    (net (code "98") (name "Net-(LED4-+)") (class "Default")
      (node (ref "LED4") (pin "1") (pinfunction "+_1") (pintype "unspecified"))
      (node (ref "R16") (pin "2") (pinfunction "2_2") (pintype "unspecified"))
    )
    (net (code "99") (name "Net-(LED4--)") (class "Default")
      (node (ref "CN1") (pin "2") (pinfunction "2_2") (pintype "unspecified"))
      (node (ref "LED4") (pin "2") (pinfunction "-_2") (pintype "unspecified"))
      (node (ref "U19") (pin "17") (pinfunction "2C_17") (pintype "unspecified"))
    )
    (net (code "100") (name "Net-(LED5-+)") (class "Default")
      (node (ref "LED5") (pin "1") (pinfunction "+_1") (pintype "unspecified"))
      (node (ref "R17") (pin "2") (pinfunction "2_2") (pintype "unspecified"))
    )
    (net (code "101") (name "Net-(LED5--)") (class "Default")
      (node (ref "CN1") (pin "3") (pinfunction "3_3") (pintype "unspecified"))
      (node (ref "LED5") (pin "2") (pinfunction "-_2") (pintype "unspecified"))
      (node (ref "U19") (pin "16") (pinfunction "3C_16") (pintype "unspecified"))
    )
    (net (code "102") (name "Net-(LED6-+)") (class "Default")
      (node (ref "LED6") (pin "1") (pinfunction "+_1") (pintype "unspecified"))
      (node (ref "R18") (pin "2") (pinfunction "2_2") (pintype "unspecified"))
    )
    (net (code "103") (name "Net-(LED6--)") (class "Default")
      (node (ref "CN1") (pin "4") (pinfunction "4_4") (pintype "unspecified"))
      (node (ref "LED6") (pin "2") (pinfunction "-_2") (pintype "unspecified"))
      (node (ref "U19") (pin "15") (pinfunction "4C_15") (pintype "unspecified"))
    )
    (net (code "104") (name "Net-(OLED1-GND)") (class "Default")
      (node (ref "OLED1") (pin "1") (pinfunction "GND_1") (pintype "unspecified"))
      (node (ref "SW34") (pin "4") (pinfunction "PIN4_4") (pintype "unspecified"))
    )
    (net (code "105") (name "Net-(OLED1-SCL)") (class "Default")
      (node (ref "OLED1") (pin "3") (pinfunction "SCL_3") (pintype "unspecified"))
      (node (ref "SW34") (pin "2") (pinfunction "PIN2_2") (pintype "unspecified"))
    )
    (net (code "106") (name "Net-(OLED1-SDA)") (class "Default")
      (node (ref "OLED1") (pin "4") (pinfunction "SDA_4") (pintype "unspecified"))
      (node (ref "SW34") (pin "1") (pinfunction "PIN1_1") (pintype "unspecified"))
    )
    (net (code "107") (name "Net-(OLED1-VCC)") (class "Default")
      (node (ref "OLED1") (pin "2") (pinfunction "VCC_2") (pintype "unspecified"))
      (node (ref "SW34") (pin "3") (pinfunction "PIN3_3") (pintype "unspecified"))
    )
    (net (code "108") (name "Net-(Q1-S)") (class "Default")
      (node (ref "Q1") (pin "2") (pinfunction "S_2") (pintype "unspecified"))
      (node (ref "U22") (pin "12") (pinfunction "DIG1_12") (pintype "unspecified"))
    )
    (net (code "109") (name "Net-(Q2-S)") (class "Default")
      (node (ref "Q2") (pin "2") (pinfunction "S_2") (pintype "unspecified"))
      (node (ref "U22") (pin "9") (pinfunction "DIG2_9") (pintype "unspecified"))
    )
    (net (code "110") (name "Net-(Q3-S)") (class "Default")
      (node (ref "Q3") (pin "2") (pinfunction "S_2") (pintype "unspecified"))
      (node (ref "U22") (pin "8") (pinfunction "DIG3_8") (pintype "unspecified"))
    )
    (net (code "111") (name "Net-(Q4-S)") (class "Default")
      (node (ref "Q4") (pin "2") (pinfunction "S_2") (pintype "unspecified"))
      (node (ref "U22") (pin "6") (pinfunction "DIG4_6") (pintype "unspecified"))
    )
    (net (code "112") (name "Net-(RN1-Pad2)") (class "Default")
      (node (ref "RN1") (pin "2") (pinfunction "2_2") (pintype "unspecified"))
      (node (ref "SW3") (pin "16") (pinfunction "16_16") (pintype "input"))
    )
    (net (code "113") (name "Net-(RN1-Pad3)") (class "Default")
      (node (ref "RN1") (pin "3") (pinfunction "3_3") (pintype "unspecified"))
      (node (ref "SW3") (pin "15") (pinfunction "15_15") (pintype "input"))
    )
    (net (code "114") (name "Net-(RN1-Pad4)") (class "Default")
      (node (ref "RN1") (pin "4") (pinfunction "4_4") (pintype "unspecified"))
      (node (ref "SW3") (pin "14") (pinfunction "14_14") (pintype "input"))
    )
    (net (code "115") (name "Net-(RN1-Pad5)") (class "Default")
      (node (ref "RN1") (pin "5") (pinfunction "5_5") (pintype "unspecified"))
      (node (ref "SW3") (pin "13") (pinfunction "13_13") (pintype "input"))
    )
    (net (code "116") (name "Net-(RN1-Pad6)") (class "Default")
      (node (ref "RN1") (pin "6") (pinfunction "6_6") (pintype "unspecified"))
      (node (ref "SW3") (pin "12") (pinfunction "12_12") (pintype "input"))
    )
    (net (code "117") (name "Net-(RN1-Pad7)") (class "Default")
      (node (ref "RN1") (pin "7") (pinfunction "7_7") (pintype "unspecified"))
      (node (ref "SW3") (pin "11") (pinfunction "11_11") (pintype "input"))
    )
    (net (code "118") (name "Net-(RN1-Pad8)") (class "Default")
      (node (ref "RN1") (pin "8") (pinfunction "8_8") (pintype "unspecified"))
      (node (ref "SW3") (pin "10") (pinfunction "10_10") (pintype "input"))
    )
    (net (code "119") (name "Net-(RN1-Pad9)") (class "Default")
      (node (ref "RN1") (pin "9") (pinfunction "9_9") (pintype "unspecified"))
      (node (ref "SW3") (pin "9") (pinfunction "9_9") (pintype "input"))
    )
    (net (code "120") (name "Net-(SW2-PIN1)") (class "Default")
      (node (ref "SW2") (pin "1") (pinfunction "PIN1_1") (pintype "unspecified"))
      (node (ref "U2") (pin "8") (pinfunction "VCC_8") (pintype "unspecified"))
      (node (ref "U3") (pin "8") (pinfunction "VCC_8") (pintype "unspecified"))
    )
    (net (code "121") (name "Net-(SW2-PIN2)") (class "Default")
      (node (ref "R5") (pin "2") (pinfunction "2_2") (pintype "unspecified"))
      (node (ref "SW2") (pin "2") (pinfunction "PIN2_2") (pintype "unspecified"))
      (node (ref "U2") (pin "7") (pinfunction "WP_7") (pintype "unspecified"))
      (node (ref "U3") (pin "7") (pinfunction "WP_7") (pintype "unspecified"))
    )
    (net (code "122") (name "Net-(SW2-PIN3)") (class "Default")
      (node (ref "SW2") (pin "3") (pinfunction "PIN3_3") (pintype "unspecified"))
      (node (ref "U2") (pin "6") (pinfunction "SCL_6") (pintype "unspecified"))
      (node (ref "U3") (pin "6") (pinfunction "SCL_6") (pintype "unspecified"))
    )
    (net (code "123") (name "Net-(SW2-PIN4)") (class "Default")
      (node (ref "SW2") (pin "4") (pinfunction "PIN4_4") (pintype "unspecified"))
      (node (ref "U2") (pin "5") (pinfunction "SDA_5") (pintype "unspecified"))
      (node (ref "U3") (pin "5") (pinfunction "SDA_5") (pintype "unspecified"))
    )
    (net (code "124") (name "Net-(SW2-PIN5)") (class "Default")
      (node (ref "H1") (pin "1") (pinfunction "1_1") (pintype "unspecified"))
      (node (ref "H1") (pin "3") (pinfunction "3_3") (pintype "unspecified"))
      (node (ref "H1") (pin "5") (pinfunction "5_5") (pintype "unspecified"))
      (node (ref "H2") (pin "1") (pinfunction "1_1") (pintype "unspecified"))
      (node (ref "H2") (pin "3") (pinfunction "3_3") (pintype "unspecified"))
      (node (ref "H2") (pin "5") (pinfunction "5_5") (pintype "unspecified"))
      (node (ref "R5") (pin "1") (pinfunction "1_1") (pintype "unspecified"))
      (node (ref "SW2") (pin "5") (pinfunction "PIN5_5") (pintype "unspecified"))
      (node (ref "U2") (pin "4") (pinfunction "GND_4") (pintype "unspecified"))
      (node (ref "U3") (pin "4") (pinfunction "GND_4") (pintype "unspecified"))
    )
    (net (code "125") (name "Net-(SW4-PIN5)") (class "Default")
      (node (ref "SW4") (pin "5") (pinfunction "PIN5_5") (pintype "unspecified"))
      (node (ref "U4") (pin "5") (pinfunction "SDA_5") (pintype "bidirectional"))
    )
    (net (code "126") (name "Net-(SW4-PIN6)") (class "Default")
      (node (ref "SW4") (pin "6") (pinfunction "PIN6_6") (pintype "unspecified"))
      (node (ref "U4") (pin "6") (pinfunction "SCL_6") (pintype "unspecified"))
    )
    (net (code "127") (name "Net-(SW4-PIN8)") (class "Default")
      (node (ref "SW4") (pin "8") (pinfunction "PIN8_8") (pintype "unspecified"))
      (node (ref "U4") (pin "8") (pinfunction "VCC_8") (pintype "passive"))
    )
    (net (code "128") (name "Net-(SW5-PIN1)") (class "Default")
      (node (ref "SW5") (pin "1") (pinfunction "PIN1_1") (pintype "unspecified"))
      (node (ref "U20") (pin "4") (pinfunction "4_4") (pintype "unspecified"))
    )
    (net (code "129") (name "Net-(SW5-PIN2)") (class "Default")
      (node (ref "SW5") (pin "2") (pinfunction "PIN2_2") (pintype "unspecified"))
      (node (ref "U20") (pin "3") (pinfunction "3_3") (pintype "unspecified"))
    )
    (net (code "130") (name "Net-(SW5-PIN3)") (class "Default")
      (node (ref "SW5") (pin "3") (pinfunction "PIN3_3") (pintype "unspecified"))
      (node (ref "U20") (pin "2") (pinfunction "2_2") (pintype "unspecified"))
    )
    (net (code "131") (name "Net-(SW5-PIN4)") (class "Default")
      (node (ref "SW5") (pin "4") (pinfunction "PIN4_4") (pintype "unspecified"))
      (node (ref "U20") (pin "1") (pinfunction "1_1") (pintype "unspecified"))
    )
    (net (code "132") (name "Net-(SW6-PIN1)") (class "Default")
      (node (ref "SW6") (pin "1") (pinfunction "PIN1_1") (pintype "unspecified"))
      (node (ref "U10") (pin "3") (pinfunction "3_3") (pintype "unspecified"))
    )
    (net (code "133") (name "Net-(SW6-PIN7)") (class "Default")
      (node (ref "SW6") (pin "7") (pinfunction "PIN7_7") (pintype "unspecified"))
      (node (ref "U18") (pin "3") (pinfunction "3_3") (pintype "unspecified"))
    )
    (net (code "134") (name "Net-(SW8-PIN2)") (class "Default")
      (node (ref "SW8") (pin "2") (pinfunction "PIN2_2") (pintype "unspecified"))
      (node (ref "U19") (pin "4") (pinfunction "4B_4") (pintype "unspecified"))
    )
    (net (code "135") (name "Net-(SW8-PIN3)") (class "Default")
      (node (ref "SW8") (pin "3") (pinfunction "PIN3_3") (pintype "unspecified"))
      (node (ref "U19") (pin "3") (pinfunction "3B_3") (pintype "unspecified"))
    )
    (net (code "136") (name "Net-(SW8-PIN4)") (class "Default")
      (node (ref "SW8") (pin "4") (pinfunction "PIN4_4") (pintype "unspecified"))
      (node (ref "U19") (pin "2") (pinfunction "2B_2") (pintype "unspecified"))
    )
    (net (code "137") (name "Net-(SW8-PIN5)") (class "Default")
      (node (ref "SW8") (pin "5") (pinfunction "PIN5_5") (pintype "unspecified"))
      (node (ref "U19") (pin "1") (pinfunction "1B_1") (pintype "unspecified"))
    )
    (net (code "138") (name "Net-(SW11-A1)") (class "Default")
      (node (ref "SW11") (pin "1") (pinfunction "A1_1") (pintype "input"))
      (node (ref "U29") (pin "8") (pinfunction "8B_8") (pintype "unspecified"))
    )
    (net (code "139") (name "Net-(SW11-A2)") (class "Default")
      (node (ref "SW11") (pin "2") (pinfunction "A2_2") (pintype "input"))
      (node (ref "U29") (pin "7") (pinfunction "7B_7") (pintype "unspecified"))
    )
    (net (code "140") (name "Net-(SW11-A3)") (class "Default")
      (node (ref "SW11") (pin "3") (pinfunction "A3_3") (pintype "input"))
      (node (ref "U29") (pin "6") (pinfunction "6B_6") (pintype "unspecified"))
    )
    (net (code "141") (name "Net-(SW11-A4)") (class "Default")
      (node (ref "SW11") (pin "4") (pinfunction "A4_4") (pintype "input"))
      (node (ref "U29") (pin "5") (pinfunction "5B_5") (pintype "unspecified"))
    )
    (net (code "142") (name "Net-(SW11-A5)") (class "Default")
      (node (ref "SW11") (pin "5") (pinfunction "A5_5") (pintype "input"))
      (node (ref "U29") (pin "4") (pinfunction "4B_4") (pintype "unspecified"))
    )
    (net (code "143") (name "Net-(SW11-A6)") (class "Default")
      (node (ref "SW11") (pin "6") (pinfunction "A6_6") (pintype "input"))
      (node (ref "U29") (pin "3") (pinfunction "3B_3") (pintype "unspecified"))
    )
    (net (code "144") (name "Net-(SW11-A7)") (class "Default")
      (node (ref "SW11") (pin "7") (pinfunction "A7_7") (pintype "input"))
      (node (ref "U29") (pin "2") (pinfunction "2B_2") (pintype "unspecified"))
    )
    (net (code "145") (name "Net-(SW11-A8)") (class "Default")
      (node (ref "SW11") (pin "8") (pinfunction "A8_8") (pintype "input"))
      (node (ref "U29") (pin "1") (pinfunction "1B_1") (pintype "unspecified"))
    )
    (net (code "146") (name "Net-(SW12-Pad2)") (class "Default")
      (node (ref "SW12") (pin "2") (pinfunction "2_2") (pintype "unspecified"))
      (node (ref "U42") (pin "2") (pinfunction "2_2") (pintype "unspecified"))
    )
    (net (code "147") (name "Net-(SW13-Pad2)") (class "Default")
      (node (ref "SW13") (pin "2") (pinfunction "2_2") (pintype "unspecified"))
      (node (ref "U43") (pin "2") (pinfunction "2_2") (pintype "unspecified"))
    )
    (net (code "148") (name "Net-(SW14-Pad2)") (class "Default")
      (node (ref "SW14") (pin "2") (pinfunction "2_2") (pintype "unspecified"))
      (node (ref "U44") (pin "2") (pinfunction "2_2") (pintype "unspecified"))
    )
    (net (code "149") (name "Net-(SW15-Pad2)") (class "Default")
      (node (ref "SW15") (pin "2") (pinfunction "2_2") (pintype "unspecified"))
      (node (ref "U45") (pin "2") (pinfunction "2_2") (pintype "unspecified"))
    )
    (net (code "150") (name "Net-(SW16-Pad1)") (class "Default")
      (node (ref "SW16") (pin "1") (pinfunction "1_1") (pintype "unspecified"))
      (node (ref "SW17") (pin "1") (pinfunction "1_1") (pintype "unspecified"))
      (node (ref "SW18") (pin "1") (pinfunction "1_1") (pintype "unspecified"))
      (node (ref "SW19") (pin "1") (pinfunction "1_1") (pintype "unspecified"))
    )
    (net (code "151") (name "Net-(SW20-Pad1)") (class "Default")
      (node (ref "SW20") (pin "1") (pinfunction "1_1") (pintype "unspecified"))
      (node (ref "SW21") (pin "1") (pinfunction "1_1") (pintype "unspecified"))
      (node (ref "SW23") (pin "1") (pinfunction "1_1") (pintype "unspecified"))
      (node (ref "SW24") (pin "1") (pinfunction "1_1") (pintype "unspecified"))
    )
    (net (code "152") (name "Net-(SW22-PIN1)") (class "Default")
      (node (ref "SW12") (pin "1") (pinfunction "1_1") (pintype "unspecified"))
      (node (ref "SW22") (pin "1") (pinfunction "PIN1_1") (pintype "unspecified"))
    )
    (net (code "153") (name "Net-(SW22-PIN2)") (class "Default")
      (node (ref "SW13") (pin "1") (pinfunction "1_1") (pintype "unspecified"))
      (node (ref "SW22") (pin "2") (pinfunction "PIN2_2") (pintype "unspecified"))
    )
    (net (code "154") (name "Net-(SW22-PIN3)") (class "Default")
      (node (ref "SW14") (pin "1") (pinfunction "1_1") (pintype "unspecified"))
      (node (ref "SW22") (pin "3") (pinfunction "PIN3_3") (pintype "unspecified"))
    )
    (net (code "155") (name "Net-(SW22-PIN4)") (class "Default")
      (node (ref "SW15") (pin "1") (pinfunction "1_1") (pintype "unspecified"))
      (node (ref "SW22") (pin "4") (pinfunction "PIN4_4") (pintype "unspecified"))
    )
    (net (code "156") (name "Net-(SW25-Pad1)") (class "Default")
      (node (ref "SW25") (pin "1") (pinfunction "1_1") (pintype "unspecified"))
      (node (ref "SW26") (pin "1") (pinfunction "1_1") (pintype "unspecified"))
      (node (ref "SW27") (pin "1") (pinfunction "1_1") (pintype "unspecified"))
      (node (ref "SW28") (pin "1") (pinfunction "1_1") (pintype "unspecified"))
    )
    (net (code "157") (name "Net-(SW29-Pad1)") (class "Default")
      (node (ref "SW29") (pin "1") (pinfunction "1_1") (pintype "unspecified"))
      (node (ref "SW30") (pin "1") (pinfunction "1_1") (pintype "unspecified"))
      (node (ref "SW31") (pin "1") (pinfunction "1_1") (pintype "unspecified"))
      (node (ref "SW32") (pin "1") (pinfunction "1_1") (pintype "unspecified"))
    )
    (net (code "158") (name "Net-(SW33-A1)") (class "Default")
      (node (ref "SW19") (pin "2") (pinfunction "2_2") (pintype "unspecified"))
      (node (ref "SW33") (pin "1") (pinfunction "A1_1") (pintype "input"))
    )
    (net (code "159") (name "Net-(SW33-A2)") (class "Default")
      (node (ref "SW20") (pin "2") (pinfunction "2_2") (pintype "unspecified"))
      (node (ref "SW33") (pin "2") (pinfunction "A2_2") (pintype "input"))
    )
    (net (code "160") (name "Net-(SW33-A3)") (class "Default")
      (node (ref "SW25") (pin "2") (pinfunction "2_2") (pintype "unspecified"))
      (node (ref "SW33") (pin "3") (pinfunction "A3_3") (pintype "input"))
    )
    (net (code "161") (name "Net-(SW33-A4)") (class "Default")
      (node (ref "SW29") (pin "2") (pinfunction "2_2") (pintype "unspecified"))
      (node (ref "SW33") (pin "4") (pinfunction "A4_4") (pintype "input"))
    )
    (net (code "162") (name "Net-(SW33-A5)") (class "Default")
      (node (ref "SW19") (pin "4") (pinfunction "4_4") (pintype "unspecified"))
      (node (ref "SW20") (pin "4") (pinfunction "4_4") (pintype "unspecified"))
      (node (ref "SW25") (pin "4") (pinfunction "4_4") (pintype "unspecified"))
      (node (ref "SW29") (pin "4") (pinfunction "4_4") (pintype "unspecified"))
      (node (ref "SW33") (pin "5") (pinfunction "A5_5") (pintype "input"))
    )
    (net (code "163") (name "Net-(SW33-A6)") (class "Default")
      (node (ref "SW18") (pin "4") (pinfunction "4_4") (pintype "unspecified"))
      (node (ref "SW21") (pin "4") (pinfunction "4_4") (pintype "unspecified"))
      (node (ref "SW26") (pin "4") (pinfunction "4_4") (pintype "unspecified"))
      (node (ref "SW30") (pin "4") (pinfunction "4_4") (pintype "unspecified"))
      (node (ref "SW33") (pin "6") (pinfunction "A6_6") (pintype "input"))
    )
    (net (code "164") (name "Net-(SW33-A7)") (class "Default")
      (node (ref "SW17") (pin "4") (pinfunction "4_4") (pintype "unspecified"))
      (node (ref "SW23") (pin "4") (pinfunction "4_4") (pintype "unspecified"))
      (node (ref "SW27") (pin "4") (pinfunction "4_4") (pintype "unspecified"))
      (node (ref "SW31") (pin "4") (pinfunction "4_4") (pintype "unspecified"))
      (node (ref "SW33") (pin "7") (pinfunction "A7_7") (pintype "input"))
    )
    (net (code "165") (name "Net-(SW33-A8)") (class "Default")
      (node (ref "SW16") (pin "4") (pinfunction "4_4") (pintype "unspecified"))
      (node (ref "SW24") (pin "4") (pinfunction "4_4") (pintype "unspecified"))
      (node (ref "SW28") (pin "4") (pinfunction "4_4") (pintype "unspecified"))
      (node (ref "SW32") (pin "4") (pinfunction "4_4") (pintype "unspecified"))
      (node (ref "SW33") (pin "8") (pinfunction "A8_8") (pintype "input"))
    )
    (net (code "166") (name "Net-(SW35-A1)") (class "Default")
      (node (ref "SW35") (pin "1") (pinfunction "A1_1") (pintype "input"))
      (node (ref "U6") (pin "3") (pinfunction "GND_3") (pintype "unspecified"))
    )
    (net (code "167") (name "Net-(SW35-A2)") (class "Default")
      (node (ref "SW35") (pin "2") (pinfunction "A2_2") (pintype "input"))
      (node (ref "U6") (pin "2") (pinfunction "Vcc_2") (pintype "unspecified"))
    )
    (net (code "168") (name "Net-(SW35-A3)") (class "Default")
      (node (ref "SW35") (pin "3") (pinfunction "A3_3") (pintype "input"))
      (node (ref "U6") (pin "1") (pinfunction "S_1") (pintype "unspecified"))
    )
    (net (code "169") (name "Net-(U2-A0)") (class "Default")
      (node (ref "H1") (pin "2") (pinfunction "2_2") (pintype "unspecified"))
      (node (ref "R9") (pin "1") (pinfunction "1_1") (pintype "unspecified"))
      (node (ref "U2") (pin "1") (pinfunction "A0_1") (pintype "unspecified"))
    )
    (net (code "170") (name "Net-(U2-A1)") (class "Default")
      (node (ref "H1") (pin "4") (pinfunction "4_4") (pintype "unspecified"))
      (node (ref "R10") (pin "1") (pinfunction "1_1") (pintype "unspecified"))
      (node (ref "U2") (pin "2") (pinfunction "A1_2") (pintype "unspecified"))
    )
    (net (code "171") (name "Net-(U2-A2)") (class "Default")
      (node (ref "H1") (pin "6") (pinfunction "6_6") (pintype "unspecified"))
      (node (ref "R11") (pin "1") (pinfunction "1_1") (pintype "unspecified"))
      (node (ref "U2") (pin "3") (pinfunction "A2_3") (pintype "unspecified"))
    )
    (net (code "172") (name "Net-(U3-A0)") (class "Default")
      (node (ref "H2") (pin "2") (pinfunction "2_2") (pintype "unspecified"))
      (node (ref "R6") (pin "1") (pinfunction "1_1") (pintype "unspecified"))
      (node (ref "U3") (pin "1") (pinfunction "A0_1") (pintype "unspecified"))
    )
    (net (code "173") (name "Net-(U3-A1)") (class "Default")
      (node (ref "H2") (pin "4") (pinfunction "4_4") (pintype "unspecified"))
      (node (ref "R7") (pin "1") (pinfunction "1_1") (pintype "unspecified"))
      (node (ref "U3") (pin "2") (pinfunction "A1_2") (pintype "unspecified"))
    )
    (net (code "174") (name "Net-(U3-A2)") (class "Default")
      (node (ref "H2") (pin "6") (pinfunction "6_6") (pintype "unspecified"))
      (node (ref "R8") (pin "1") (pinfunction "1_1") (pintype "unspecified"))
      (node (ref "U3") (pin "3") (pinfunction "A2_3") (pintype "unspecified"))
    )
    (net (code "175") (name "Net-(U4-VBAT)") (class "Default")
      (node (ref "BAT1") (pin "1") (pinfunction "1_1") (pintype "input"))
      (node (ref "U4") (pin "3") (pinfunction "VBAT_3") (pintype "passive"))
    )
    (net (code "176") (name "Net-(U4-X1)") (class "Default")
      (node (ref "U4") (pin "1") (pinfunction "X1_1") (pintype "unspecified"))
      (node (ref "U5") (pin "1") (pinfunction "OSC1_1") (pintype "input"))
    )
    (net (code "177") (name "Net-(U4-X2)") (class "Default")
      (node (ref "U4") (pin "2") (pinfunction "X2_2") (pintype "unspecified"))
      (node (ref "U5") (pin "2") (pinfunction "OSC2_2") (pintype "input"))
    )
    (net (code "178") (name "Net-(U7-OUTPUT)") (class "Default")
      (node (ref "L1") (pin "1") (pinfunction "1_1") (pintype "unspecified"))
      (node (ref "U7") (pin "2") (pinfunction "OUTPUT_2") (pintype "unspecified"))
    )
    (net (code "179") (name "Net-(U22-A)") (class "Default")
      (node (ref "R47") (pin "2") (pinfunction "2_2") (pintype "input"))
      (node (ref "U22") (pin "11") (pinfunction "A_11") (pintype "unspecified"))
    )
    (net (code "180") (name "Net-(U22-B)") (class "Default")
      (node (ref "R46") (pin "2") (pinfunction "2_2") (pintype "input"))
      (node (ref "U22") (pin "7") (pinfunction "B_7") (pintype "unspecified"))
    )
    (net (code "181") (name "Net-(U22-C)") (class "Default")
      (node (ref "R45") (pin "2") (pinfunction "2_2") (pintype "input"))
      (node (ref "U22") (pin "4") (pinfunction "C_4") (pintype "unspecified"))
    )
    (net (code "182") (name "Net-(U22-D)") (class "Default")
      (node (ref "R44") (pin "2") (pinfunction "2_2") (pintype "input"))
      (node (ref "U22") (pin "2") (pinfunction "D_2") (pintype "unspecified"))
    )
    (net (code "183") (name "Net-(U22-DP)") (class "Default")
      (node (ref "R40") (pin "2") (pinfunction "2_2") (pintype "input"))
      (node (ref "U22") (pin "3") (pinfunction "DP_3") (pintype "unspecified"))
    )
    (net (code "184") (name "Net-(U22-E)") (class "Default")
      (node (ref "R43") (pin "2") (pinfunction "2_2") (pintype "input"))
      (node (ref "U22") (pin "1") (pinfunction "E_1") (pintype "unspecified"))
    )
    (net (code "185") (name "Net-(U22-F)") (class "Default")
      (node (ref "R42") (pin "2") (pinfunction "2_2") (pintype "input"))
      (node (ref "U22") (pin "10") (pinfunction "F_10") (pintype "unspecified"))
    )
    (net (code "186") (name "Net-(U22-G)") (class "Default")
      (node (ref "R41") (pin "2") (pinfunction "2_2") (pintype "input"))
      (node (ref "U22") (pin "5") (pinfunction "G_5") (pintype "unspecified"))
    )
    (net (code "187") (name "Net-(U24-C1)") (class "Default")
      (node (ref "R27") (pin "1") (pinfunction "1_1") (pintype "input"))
      (node (ref "U24") (pin "13") (pinfunction "C1_13") (pintype "unspecified"))
    )
    (net (code "188") (name "Net-(U24-C2)") (class "Default")
      (node (ref "R26") (pin "1") (pinfunction "1_1") (pintype "input"))
      (node (ref "U24") (pin "3") (pinfunction "C2_3") (pintype "unspecified"))
    )
    (net (code "189") (name "Net-(U24-C3)") (class "Default")
      (node (ref "R25") (pin "1") (pinfunction "1_1") (pintype "input"))
      (node (ref "U24") (pin "4") (pinfunction "C3_4") (pintype "unspecified"))
    )
    (net (code "190") (name "Net-(U24-C4)") (class "Default")
      (node (ref "R24") (pin "1") (pinfunction "1_1") (pintype "input"))
      (node (ref "U24") (pin "10") (pinfunction "C4_10") (pintype "unspecified"))
    )
    (net (code "191") (name "Net-(U24-C5)") (class "Default")
      (node (ref "R23") (pin "1") (pinfunction "1_1") (pintype "input"))
      (node (ref "U24") (pin "6") (pinfunction "C5_6") (pintype "unspecified"))
    )
    (net (code "192") (name "Net-(U24-C6)") (class "Default")
      (node (ref "R28") (pin "1") (pinfunction "1_1") (pintype "input"))
      (node (ref "U24") (pin "11") (pinfunction "C6_11") (pintype "unspecified"))
    )
    (net (code "193") (name "Net-(U24-C7)") (class "Default")
      (node (ref "R29") (pin "1") (pinfunction "1_1") (pintype "input"))
      (node (ref "U24") (pin "15") (pinfunction "C7_15") (pintype "unspecified"))
    )
    (net (code "194") (name "Net-(U24-C8)") (class "Default")
      (node (ref "R30") (pin "1") (pinfunction "1_1") (pintype "input"))
      (node (ref "U24") (pin "16") (pinfunction "C8_16") (pintype "unspecified"))
    )
    (net (code "195") (name "Net-(U27-C1)") (class "Default")
      (node (ref "R38") (pin "1") (pinfunction "1_1") (pintype "input"))
      (node (ref "U27") (pin "13") (pinfunction "C1_13") (pintype "unspecified"))
    )
    (net (code "196") (name "Net-(U27-C2)") (class "Default")
      (node (ref "R37") (pin "1") (pinfunction "1_1") (pintype "input"))
      (node (ref "U27") (pin "3") (pinfunction "C2_3") (pintype "unspecified"))
    )
    (net (code "197") (name "Net-(U27-C3)") (class "Default")
      (node (ref "R36") (pin "1") (pinfunction "1_1") (pintype "input"))
      (node (ref "U27") (pin "4") (pinfunction "C3_4") (pintype "unspecified"))
    )
    (net (code "198") (name "Net-(U27-C4)") (class "Default")
      (node (ref "R35") (pin "1") (pinfunction "1_1") (pintype "input"))
      (node (ref "U27") (pin "10") (pinfunction "C4_10") (pintype "unspecified"))
    )
    (net (code "199") (name "Net-(U27-C5)") (class "Default")
      (node (ref "R34") (pin "1") (pinfunction "1_1") (pintype "input"))
      (node (ref "U27") (pin "6") (pinfunction "C5_6") (pintype "unspecified"))
    )
    (net (code "200") (name "Net-(U27-C6)") (class "Default")
      (node (ref "R33") (pin "1") (pinfunction "1_1") (pintype "input"))
      (node (ref "U27") (pin "11") (pinfunction "C6_11") (pintype "unspecified"))
    )
    (net (code "201") (name "Net-(U27-C7)") (class "Default")
      (node (ref "R32") (pin "1") (pinfunction "1_1") (pintype "input"))
      (node (ref "U27") (pin "15") (pinfunction "C7_15") (pintype "unspecified"))
    )
    (net (code "202") (name "Net-(U27-C8)") (class "Default")
      (node (ref "R31") (pin "1") (pinfunction "1_1") (pintype "input"))
      (node (ref "U27") (pin "16") (pinfunction "C8_16") (pintype "unspecified"))
    )
    (net (code "203") (name "Net-(U29-1C)") (class "Default")
      (node (ref "U29") (pin "18") (pinfunction "1C_18") (pintype "unspecified"))
      (node (ref "U30") (pin "2") (pinfunction "-_2") (pintype "unspecified"))
    )
    (net (code "204") (name "Net-(U29-2C)") (class "Default")
      (node (ref "U29") (pin "17") (pinfunction "2C_17") (pintype "unspecified"))
      (node (ref "U31") (pin "2") (pinfunction "-_2") (pintype "unspecified"))
    )
    (net (code "205") (name "Net-(U29-3C)") (class "Default")
      (node (ref "U29") (pin "16") (pinfunction "3C_16") (pintype "unspecified"))
      (node (ref "U32") (pin "2") (pinfunction "-_2") (pintype "unspecified"))
    )
    (net (code "206") (name "Net-(U29-4C)") (class "Default")
      (node (ref "U29") (pin "15") (pinfunction "4C_15") (pintype "unspecified"))
      (node (ref "U33") (pin "2") (pinfunction "-_2") (pintype "unspecified"))
    )
    (net (code "207") (name "Net-(U29-5C)") (class "Default")
      (node (ref "U29") (pin "14") (pinfunction "5C_14") (pintype "unspecified"))
      (node (ref "U37") (pin "2") (pinfunction "-_2") (pintype "unspecified"))
    )
    (net (code "208") (name "Net-(U29-6C)") (class "Default")
      (node (ref "U29") (pin "13") (pinfunction "6C_13") (pintype "unspecified"))
      (node (ref "U36") (pin "2") (pinfunction "-_2") (pintype "unspecified"))
    )
    (net (code "209") (name "Net-(U29-7C)") (class "Default")
      (node (ref "U29") (pin "12") (pinfunction "7C_12") (pintype "unspecified"))
      (node (ref "U35") (pin "2") (pinfunction "-_2") (pintype "unspecified"))
    )
    (net (code "210") (name "Net-(U29-8C)") (class "Default")
      (node (ref "U29") (pin "11") (pinfunction "8C_11") (pintype "unspecified"))
      (node (ref "U34") (pin "2") (pinfunction "-_2") (pintype "unspecified"))
    )
    (net (code "211") (name "Net-(U30-+)") (class "Default")
      (node (ref "R48") (pin "1") (pinfunction "1_1") (pintype "unspecified"))
      (node (ref "U30") (pin "1") (pinfunction "+_1") (pintype "unspecified"))
    )
    (net (code "212") (name "Net-(U31-+)") (class "Default")
      (node (ref "R49") (pin "1") (pinfunction "1_1") (pintype "unspecified"))
      (node (ref "U31") (pin "1") (pinfunction "+_1") (pintype "unspecified"))
    )
    (net (code "213") (name "Net-(U32-+)") (class "Default")
      (node (ref "R50") (pin "1") (pinfunction "1_1") (pintype "unspecified"))
      (node (ref "U32") (pin "1") (pinfunction "+_1") (pintype "unspecified"))
    )
    (net (code "214") (name "Net-(U33-+)") (class "Default")
      (node (ref "R51") (pin "1") (pinfunction "1_1") (pintype "unspecified"))
      (node (ref "U33") (pin "1") (pinfunction "+_1") (pintype "unspecified"))
    )
    (net (code "215") (name "Net-(U34-+)") (class "Default")
      (node (ref "R52") (pin "1") (pinfunction "1_1") (pintype "unspecified"))
      (node (ref "U34") (pin "1") (pinfunction "+_1") (pintype "unspecified"))
    )
    (net (code "216") (name "Net-(U35-+)") (class "Default")
      (node (ref "R53") (pin "1") (pinfunction "1_1") (pintype "unspecified"))
      (node (ref "U35") (pin "1") (pinfunction "+_1") (pintype "unspecified"))
    )
    (net (code "217") (name "Net-(U36-+)") (class "Default")
      (node (ref "R54") (pin "1") (pinfunction "1_1") (pintype "unspecified"))
      (node (ref "U36") (pin "1") (pinfunction "+_1") (pintype "unspecified"))
    )
    (net (code "218") (name "Net-(U37-+)") (class "Default")
      (node (ref "R55") (pin "1") (pinfunction "1_1") (pintype "unspecified"))
      (node (ref "U37") (pin "1") (pinfunction "+_1") (pintype "unspecified"))
    )
    (net (code "219") (name "Net-(U38-+VS)") (class "Default")
      (node (ref "U38") (pin "1") (pinfunction "+VS_1") (pintype "unspecified"))
      (node (ref "U39") (pin "1") (pinfunction "A1_1") (pintype "input"))
    )
    (net (code "220") (name "Net-(U38-VOUT)") (class "Default")
      (node (ref "R56") (pin "1") (pinfunction "1_1") (pintype "unspecified"))
      (node (ref "U38") (pin "2") (pinfunction "VOUT_2") (pintype "unspecified"))
    )
    (net (code "221") (name "Net-(U39-A2)") (class "Default")
      (node (ref "C7") (pin "1") (pinfunction "1_1") (pintype "unspecified"))
      (node (ref "R56") (pin "2") (pinfunction "2_2") (pintype "unspecified"))
      (node (ref "U39") (pin "2") (pinfunction "A2_2") (pintype "input"))
    )
    (net (code "222") (name "Net-(U40-DATA)") (class "Default")
      (node (ref "U40") (pin "2") (pinfunction "DATA_2") (pintype "unspecified"))
      (node (ref "U41") (pin "2") (pinfunction "A2_2") (pintype "input"))
    )
    (net (code "223") (name "Net-(U40-VDD)") (class "Default")
      (node (ref "U40") (pin "1") (pinfunction "VDD_1") (pintype "unspecified"))
      (node (ref "U41") (pin "1") (pinfunction "A1_1") (pintype "input"))
    )
    (net (code "224") (name "Vin") (class "Default")
      (node (ref "C1") (pin "1") (pinfunction "1_1") (pintype "unspecified"))
      (node (ref "D2") (pin "1") (pinfunction "K_1") (pintype "unspecified"))
      (node (ref "D3") (pin "1") (pinfunction "K_1") (pintype "unspecified"))
      (node (ref "D8") (pin "1") (pinfunction "K_1") (pintype "unspecified"))
      (node (ref "D9") (pin "1") (pinfunction "K_1") (pintype "unspecified"))
      (node (ref "U11") (pin "1") (pinfunction "1_1") (pintype "unspecified"))
      (node (ref "U12") (pin "1") (pinfunction "1_1") (pintype "unspecified"))
      (node (ref "U16") (pin "1") (pinfunction "1_1") (pintype "unspecified"))
      (node (ref "U7") (pin "1") (pinfunction "VIN_1") (pintype "unspecified"))
      (node (ref "U8") (pin "12") (pinfunction "VSS_12") (pintype "unspecified"))
    )
    (net (code "225") (name "unconnected-(IC1-STATE-Pad1)") (class "Default")
      (node (ref "IC1") (pin "1") (pinfunction "STATE_1") (pintype "unspecified+no_connect"))
    )
    (net (code "226") (name "unconnected-(SW12-Pad3)") (class "Default")
      (node (ref "SW12") (pin "3") (pinfunction "3_3") (pintype "unspecified"))
    )
    (net (code "227") (name "unconnected-(SW13-Pad3)") (class "Default")
      (node (ref "SW13") (pin "3") (pinfunction "3_3") (pintype "unspecified"))
    )
    (net (code "228") (name "unconnected-(SW14-Pad3)") (class "Default")
      (node (ref "SW14") (pin "3") (pinfunction "3_3") (pintype "unspecified"))
    )
    (net (code "229") (name "unconnected-(SW15-Pad3)") (class "Default")
      (node (ref "SW15") (pin "3") (pinfunction "3_3") (pintype "unspecified"))
    )
    (net (code "230") (name "unconnected-(SW16-Pad2)") (class "Default")
      (node (ref "SW16") (pin "2") (pinfunction "2_2") (pintype "unspecified"))
    )
    (net (code "231") (name "unconnected-(SW16-Pad3)") (class "Default")
      (node (ref "SW16") (pin "3") (pinfunction "3_3") (pintype "unspecified"))
    )
    (net (code "232") (name "unconnected-(SW17-Pad2)") (class "Default")
      (node (ref "SW17") (pin "2") (pinfunction "2_2") (pintype "unspecified"))
    )
    (net (code "233") (name "unconnected-(SW17-Pad3)") (class "Default")
      (node (ref "SW17") (pin "3") (pinfunction "3_3") (pintype "unspecified"))
    )
    (net (code "234") (name "unconnected-(SW18-Pad2)") (class "Default")
      (node (ref "SW18") (pin "2") (pinfunction "2_2") (pintype "unspecified"))
    )
    (net (code "235") (name "unconnected-(SW18-Pad3)") (class "Default")
      (node (ref "SW18") (pin "3") (pinfunction "3_3") (pintype "unspecified"))
    )
    (net (code "236") (name "unconnected-(SW19-Pad3)") (class "Default")
      (node (ref "SW19") (pin "3") (pinfunction "3_3") (pintype "unspecified"))
    )
    (net (code "237") (name "unconnected-(SW20-Pad3)") (class "Default")
      (node (ref "SW20") (pin "3") (pinfunction "3_3") (pintype "unspecified"))
    )
    (net (code "238") (name "unconnected-(SW21-Pad2)") (class "Default")
      (node (ref "SW21") (pin "2") (pinfunction "2_2") (pintype "unspecified"))
    )
    (net (code "239") (name "unconnected-(SW21-Pad3)") (class "Default")
      (node (ref "SW21") (pin "3") (pinfunction "3_3") (pintype "unspecified"))
    )
    (net (code "240") (name "unconnected-(SW23-Pad2)") (class "Default")
      (node (ref "SW23") (pin "2") (pinfunction "2_2") (pintype "unspecified"))
    )
    (net (code "241") (name "unconnected-(SW23-Pad3)") (class "Default")
      (node (ref "SW23") (pin "3") (pinfunction "3_3") (pintype "unspecified"))
    )
    (net (code "242") (name "unconnected-(SW24-Pad2)") (class "Default")
      (node (ref "SW24") (pin "2") (pinfunction "2_2") (pintype "unspecified"))
    )
    (net (code "243") (name "unconnected-(SW24-Pad3)") (class "Default")
      (node (ref "SW24") (pin "3") (pinfunction "3_3") (pintype "unspecified"))
    )
    (net (code "244") (name "unconnected-(SW25-Pad3)") (class "Default")
      (node (ref "SW25") (pin "3") (pinfunction "3_3") (pintype "unspecified"))
    )
    (net (code "245") (name "unconnected-(SW26-Pad2)") (class "Default")
      (node (ref "SW26") (pin "2") (pinfunction "2_2") (pintype "unspecified"))
    )
    (net (code "246") (name "unconnected-(SW26-Pad3)") (class "Default")
      (node (ref "SW26") (pin "3") (pinfunction "3_3") (pintype "unspecified"))
    )
    (net (code "247") (name "unconnected-(SW27-Pad2)") (class "Default")
      (node (ref "SW27") (pin "2") (pinfunction "2_2") (pintype "unspecified"))
    )
    (net (code "248") (name "unconnected-(SW27-Pad3)") (class "Default")
      (node (ref "SW27") (pin "3") (pinfunction "3_3") (pintype "unspecified"))
    )
    (net (code "249") (name "unconnected-(SW28-Pad2)") (class "Default")
      (node (ref "SW28") (pin "2") (pinfunction "2_2") (pintype "unspecified+no_connect"))
    )
    (net (code "250") (name "unconnected-(SW28-Pad3)") (class "Default")
      (node (ref "SW28") (pin "3") (pinfunction "3_3") (pintype "unspecified+no_connect"))
    )
    (net (code "251") (name "unconnected-(SW29-Pad3)") (class "Default")
      (node (ref "SW29") (pin "3") (pinfunction "3_3") (pintype "unspecified"))
    )
    (net (code "252") (name "unconnected-(SW30-Pad2)") (class "Default")
      (node (ref "SW30") (pin "2") (pinfunction "2_2") (pintype "unspecified"))
    )
    (net (code "253") (name "unconnected-(SW30-Pad3)") (class "Default")
      (node (ref "SW30") (pin "3") (pinfunction "3_3") (pintype "unspecified"))
    )
    (net (code "254") (name "unconnected-(SW31-Pad2)") (class "Default")
      (node (ref "SW31") (pin "2") (pinfunction "2_2") (pintype "unspecified"))
    )
    (net (code "255") (name "unconnected-(SW31-Pad3)") (class "Default")
      (node (ref "SW31") (pin "3") (pinfunction "3_3") (pintype "unspecified"))
    )
    (net (code "256") (name "unconnected-(SW32-Pad2)") (class "Default")
      (node (ref "SW32") (pin "2") (pinfunction "2_2") (pintype "unspecified+no_connect"))
    )
    (net (code "257") (name "unconnected-(SW32-Pad3)") (class "Default")
      (node (ref "SW32") (pin "3") (pinfunction "3_3") (pintype "unspecified+no_connect"))
    )
    (net (code "258") (name "unconnected-(U1-RST-Pad28)") (class "Default")
      (node (ref "U1") (pin "28") (pinfunction "RST_28") (pintype "unspecified+no_connect"))
    )
    (net (code "259") (name "unconnected-(U1-VIN-Pad30)") (class "Default")
      (node (ref "U1") (pin "30") (pinfunction "VIN_30") (pintype "unspecified+no_connect"))
    )
    (net (code "260") (name "unconnected-(U4-SQWOUT-Pad7)") (class "Default")
      (node (ref "U4") (pin "7") (pinfunction "SQWOUT_7") (pintype "unspecified+no_connect"))
    )
    (net (code "261") (name "unconnected-(U8-N.C.-Pad3)") (class "Default")
      (node (ref "U8") (pin "3") (pinfunction "N.C._3") (pintype "unspecified+no_connect"))
    )
    (net (code "262") (name "unconnected-(U8-N.C.-Pad18)") (class "Default")
      (node (ref "U8") (pin "18") (pinfunction "N.C._18") (pintype "unspecified+no_connect"))
    )
    (net (code "263") (name "unconnected-(U19-5B-Pad5)") (class "Default")
      (node (ref "U19") (pin "5") (pinfunction "5B_5") (pintype "unspecified+no_connect"))
    )
    (net (code "264") (name "unconnected-(U19-5C-Pad14)") (class "Default")
      (node (ref "U19") (pin "14") (pinfunction "5C_14") (pintype "unspecified+no_connect"))
    )
    (net (code "265") (name "unconnected-(U19-6B-Pad6)") (class "Default")
      (node (ref "U19") (pin "6") (pinfunction "6B_6") (pintype "unspecified+no_connect"))
    )
    (net (code "266") (name "unconnected-(U19-6C-Pad13)") (class "Default")
      (node (ref "U19") (pin "13") (pinfunction "6C_13") (pintype "unspecified+no_connect"))
    )
    (net (code "267") (name "unconnected-(U19-7B-Pad7)") (class "Default")
      (node (ref "U19") (pin "7") (pinfunction "7B_7") (pintype "unspecified+no_connect"))
    )
    (net (code "268") (name "unconnected-(U19-7C-Pad12)") (class "Default")
      (node (ref "U19") (pin "12") (pinfunction "7C_12") (pintype "unspecified+no_connect"))
    )
    (net (code "269") (name "unconnected-(U19-8B-Pad8)") (class "Default")
      (node (ref "U19") (pin "8") (pinfunction "8B_8") (pintype "unspecified+no_connect"))
    )
    (net (code "270") (name "unconnected-(U19-8C-Pad11)") (class "Default")
      (node (ref "U19") (pin "11") (pinfunction "8C_11") (pintype "unspecified+no_connect"))
    )
    (net (code "271") (name "unconnected-(U21-QH'-Pad9)") (class "Default")
      (node (ref "U21") (pin "9") (pinfunction "QH'_9") (pintype "unspecified+no_connect"))
    )
    (net (code "272") (name "unconnected-(U25-QH'-Pad9)") (class "Default")
      (node (ref "U25") (pin "9") (pinfunction "QH'_9") (pintype "unspecified+no_connect"))
    )
    (net (code "273") (name "unconnected-(U40-NC-Pad3)") (class "Default")
      (node (ref "U40") (pin "3") (pinfunction "NC_3") (pintype "unspecified+no_connect"))
    )
  )
)
